# 433.net
KiCad netlist of a schematic drawn in EasyEDA Pro
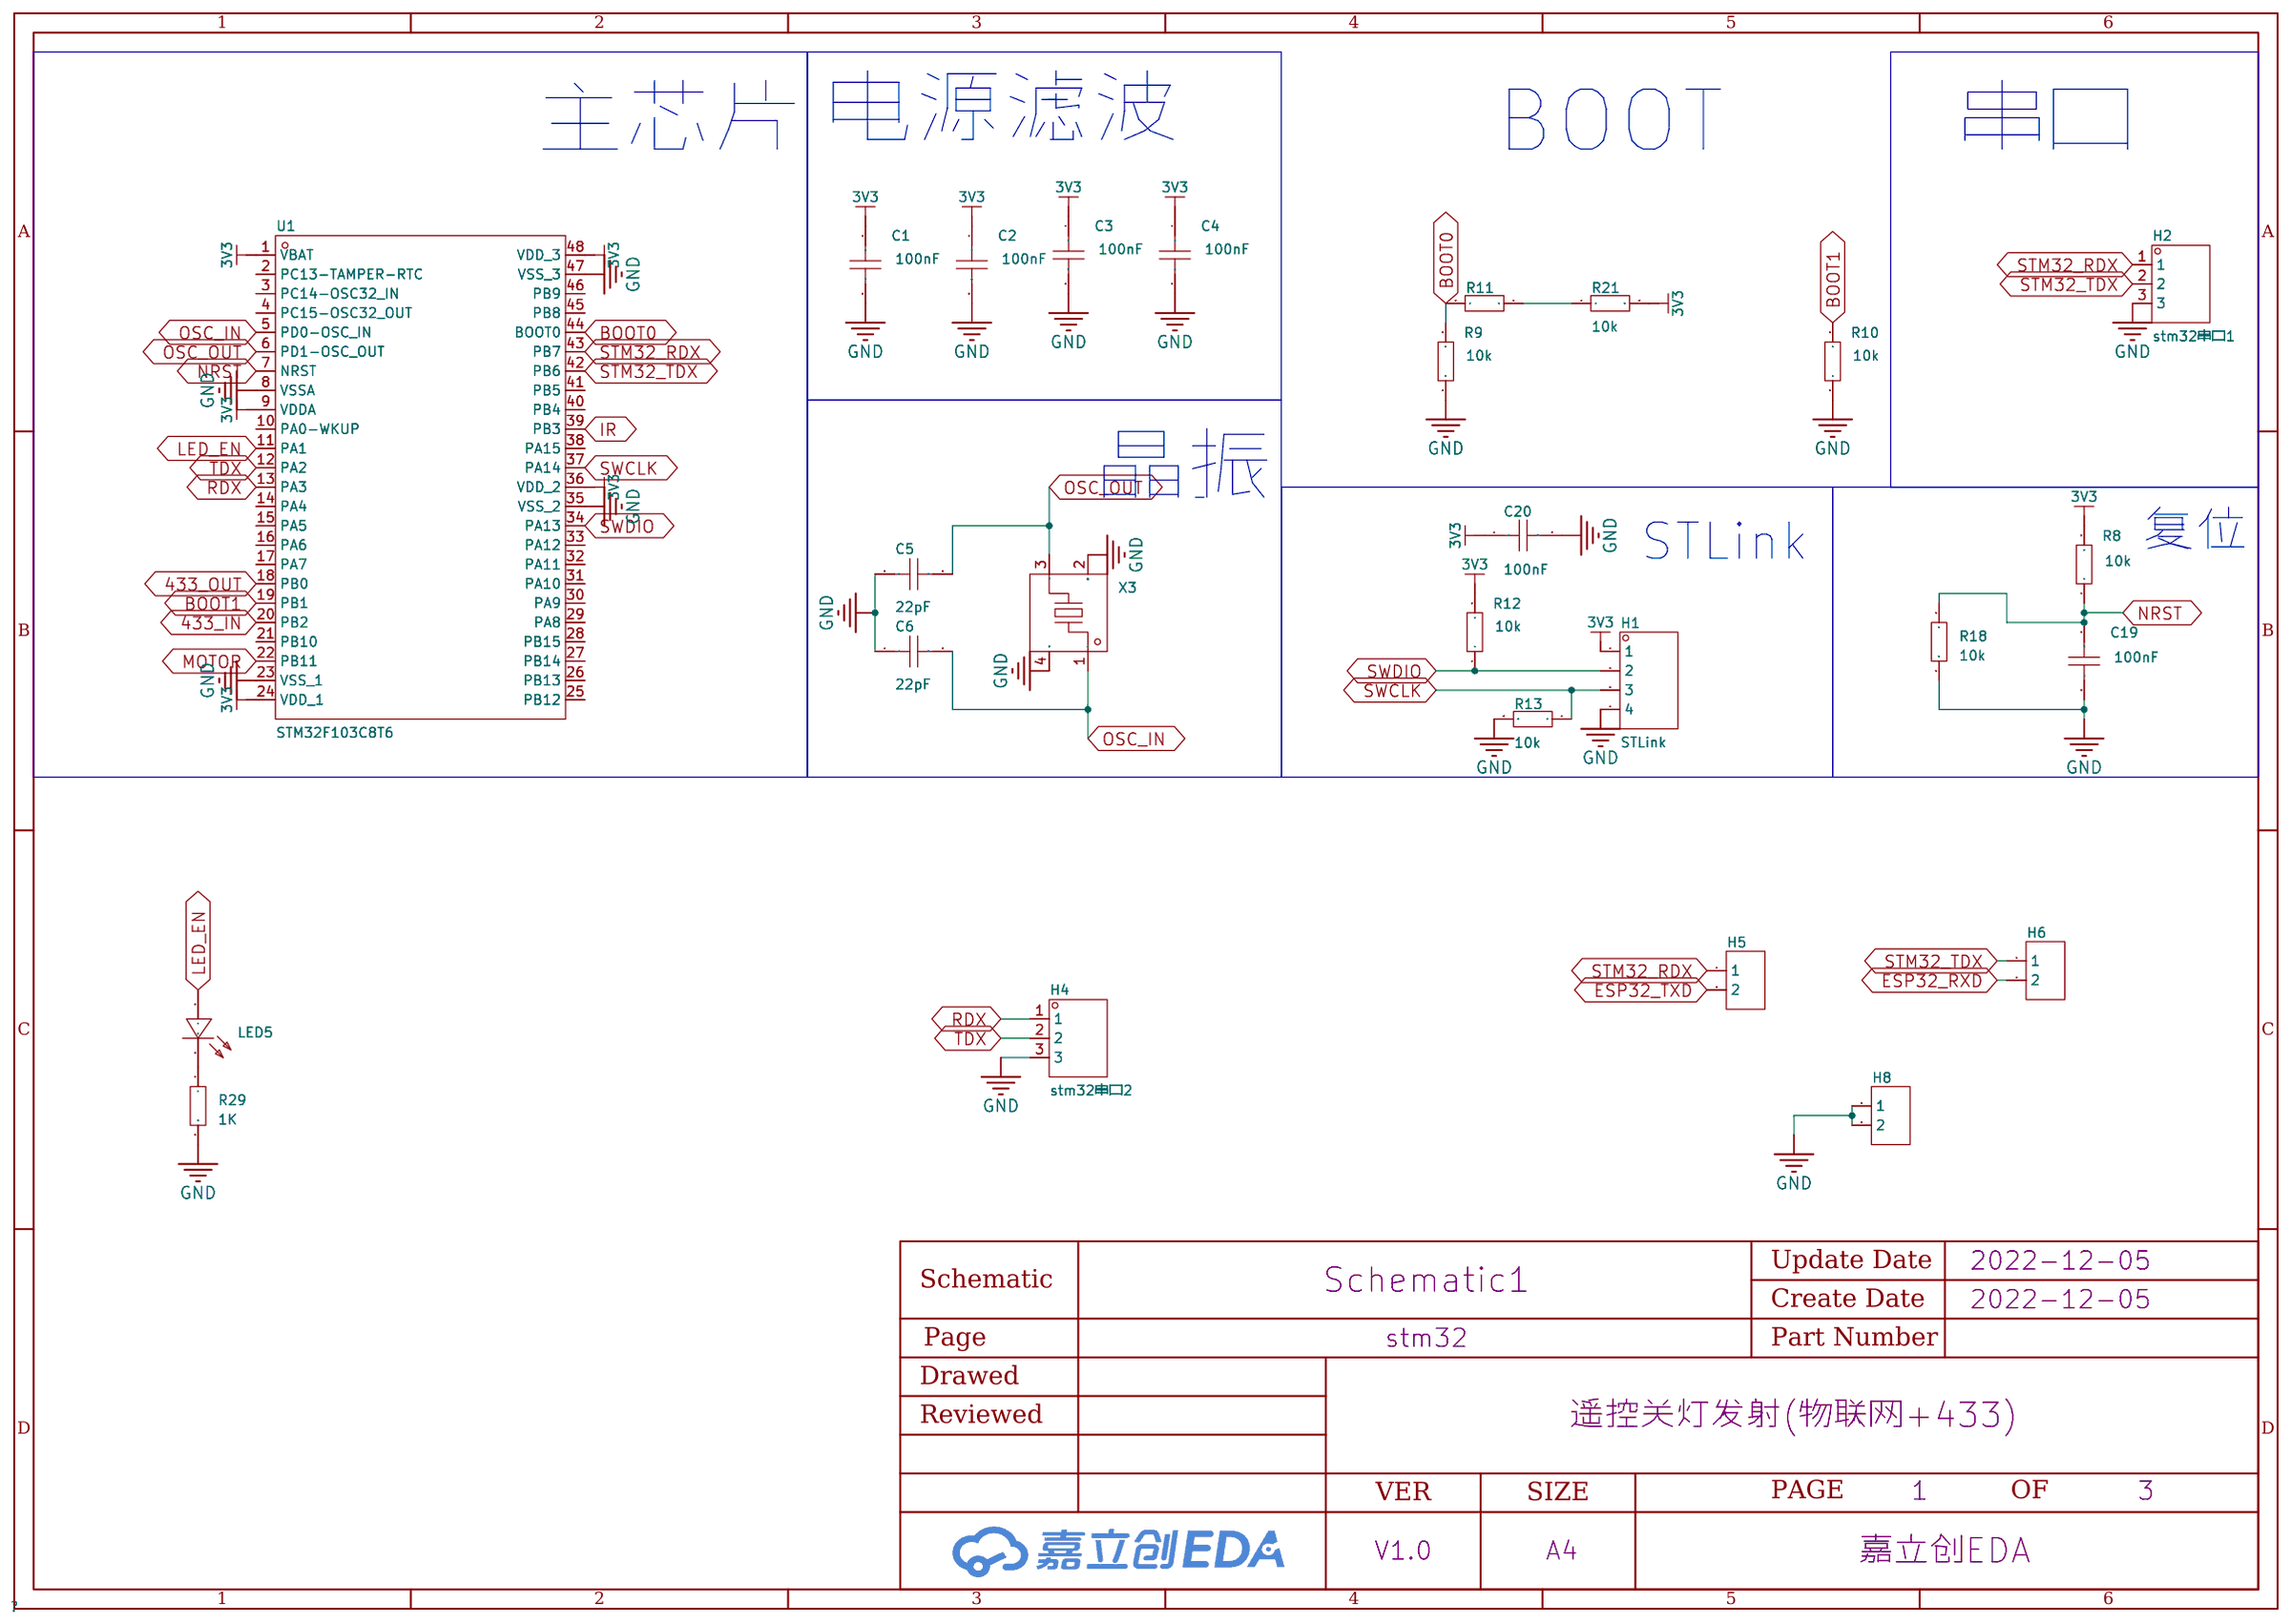
[diagram p0: stm32]
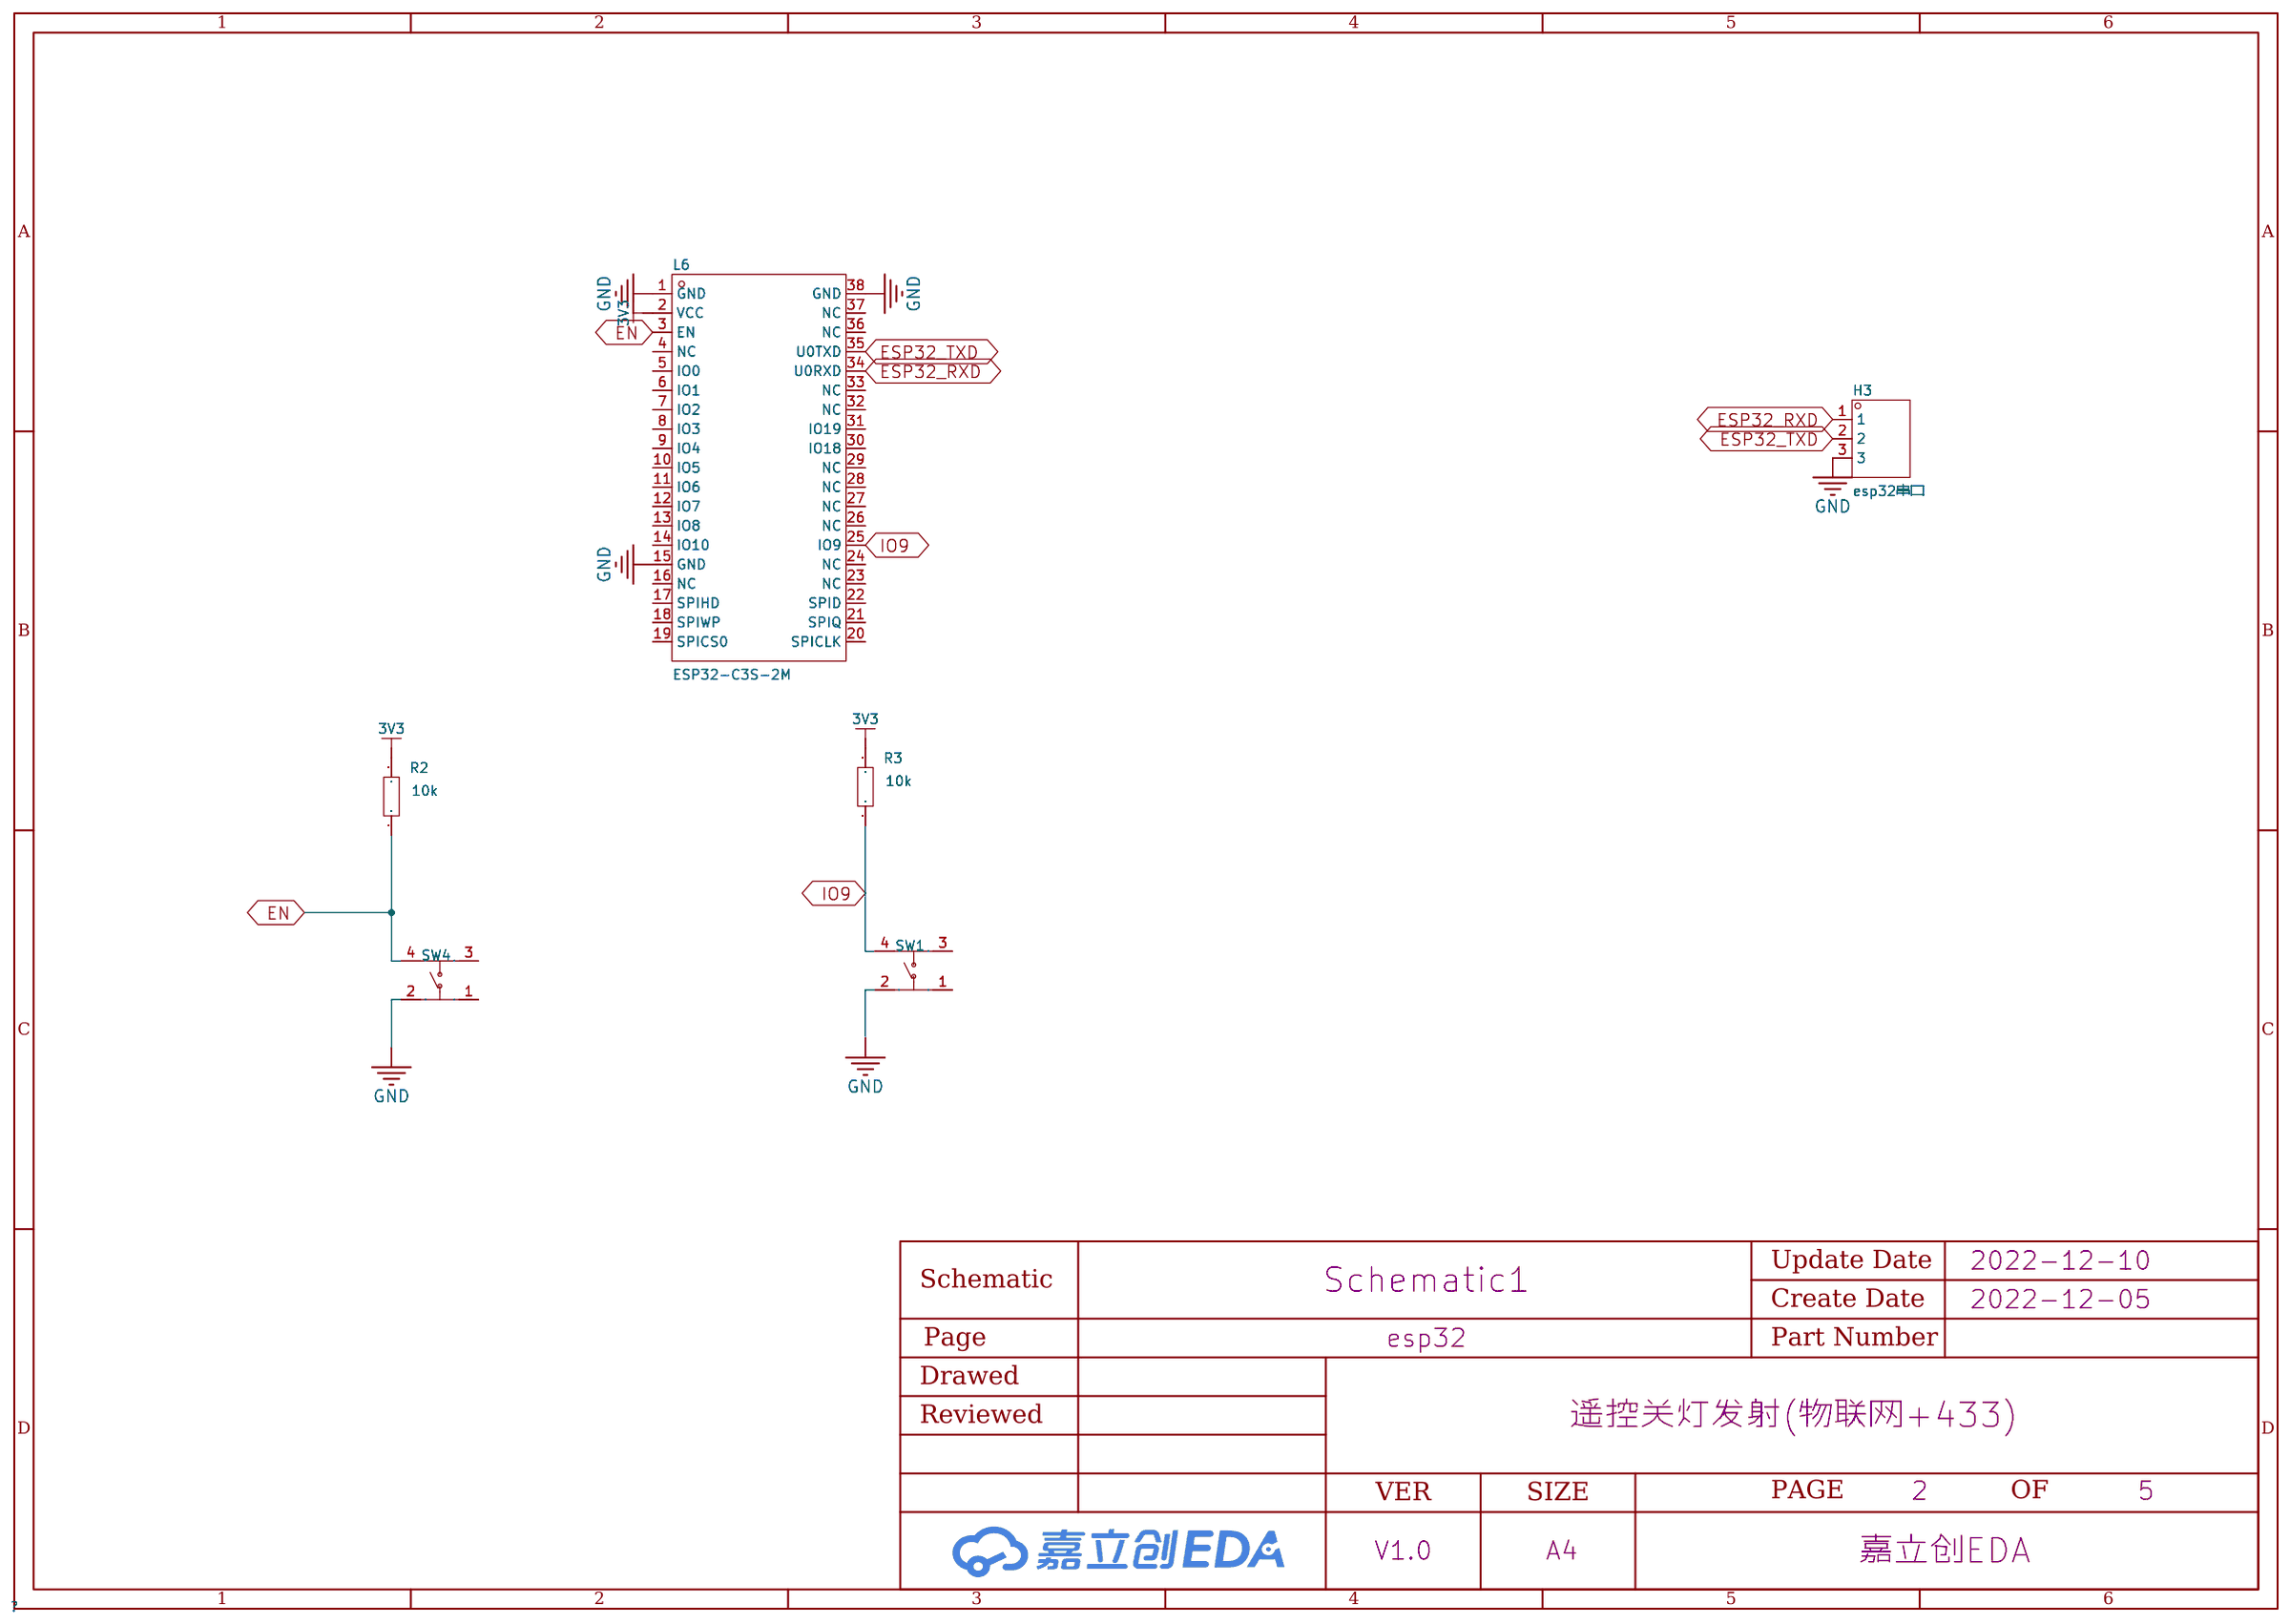
[diagram p1: esp32]
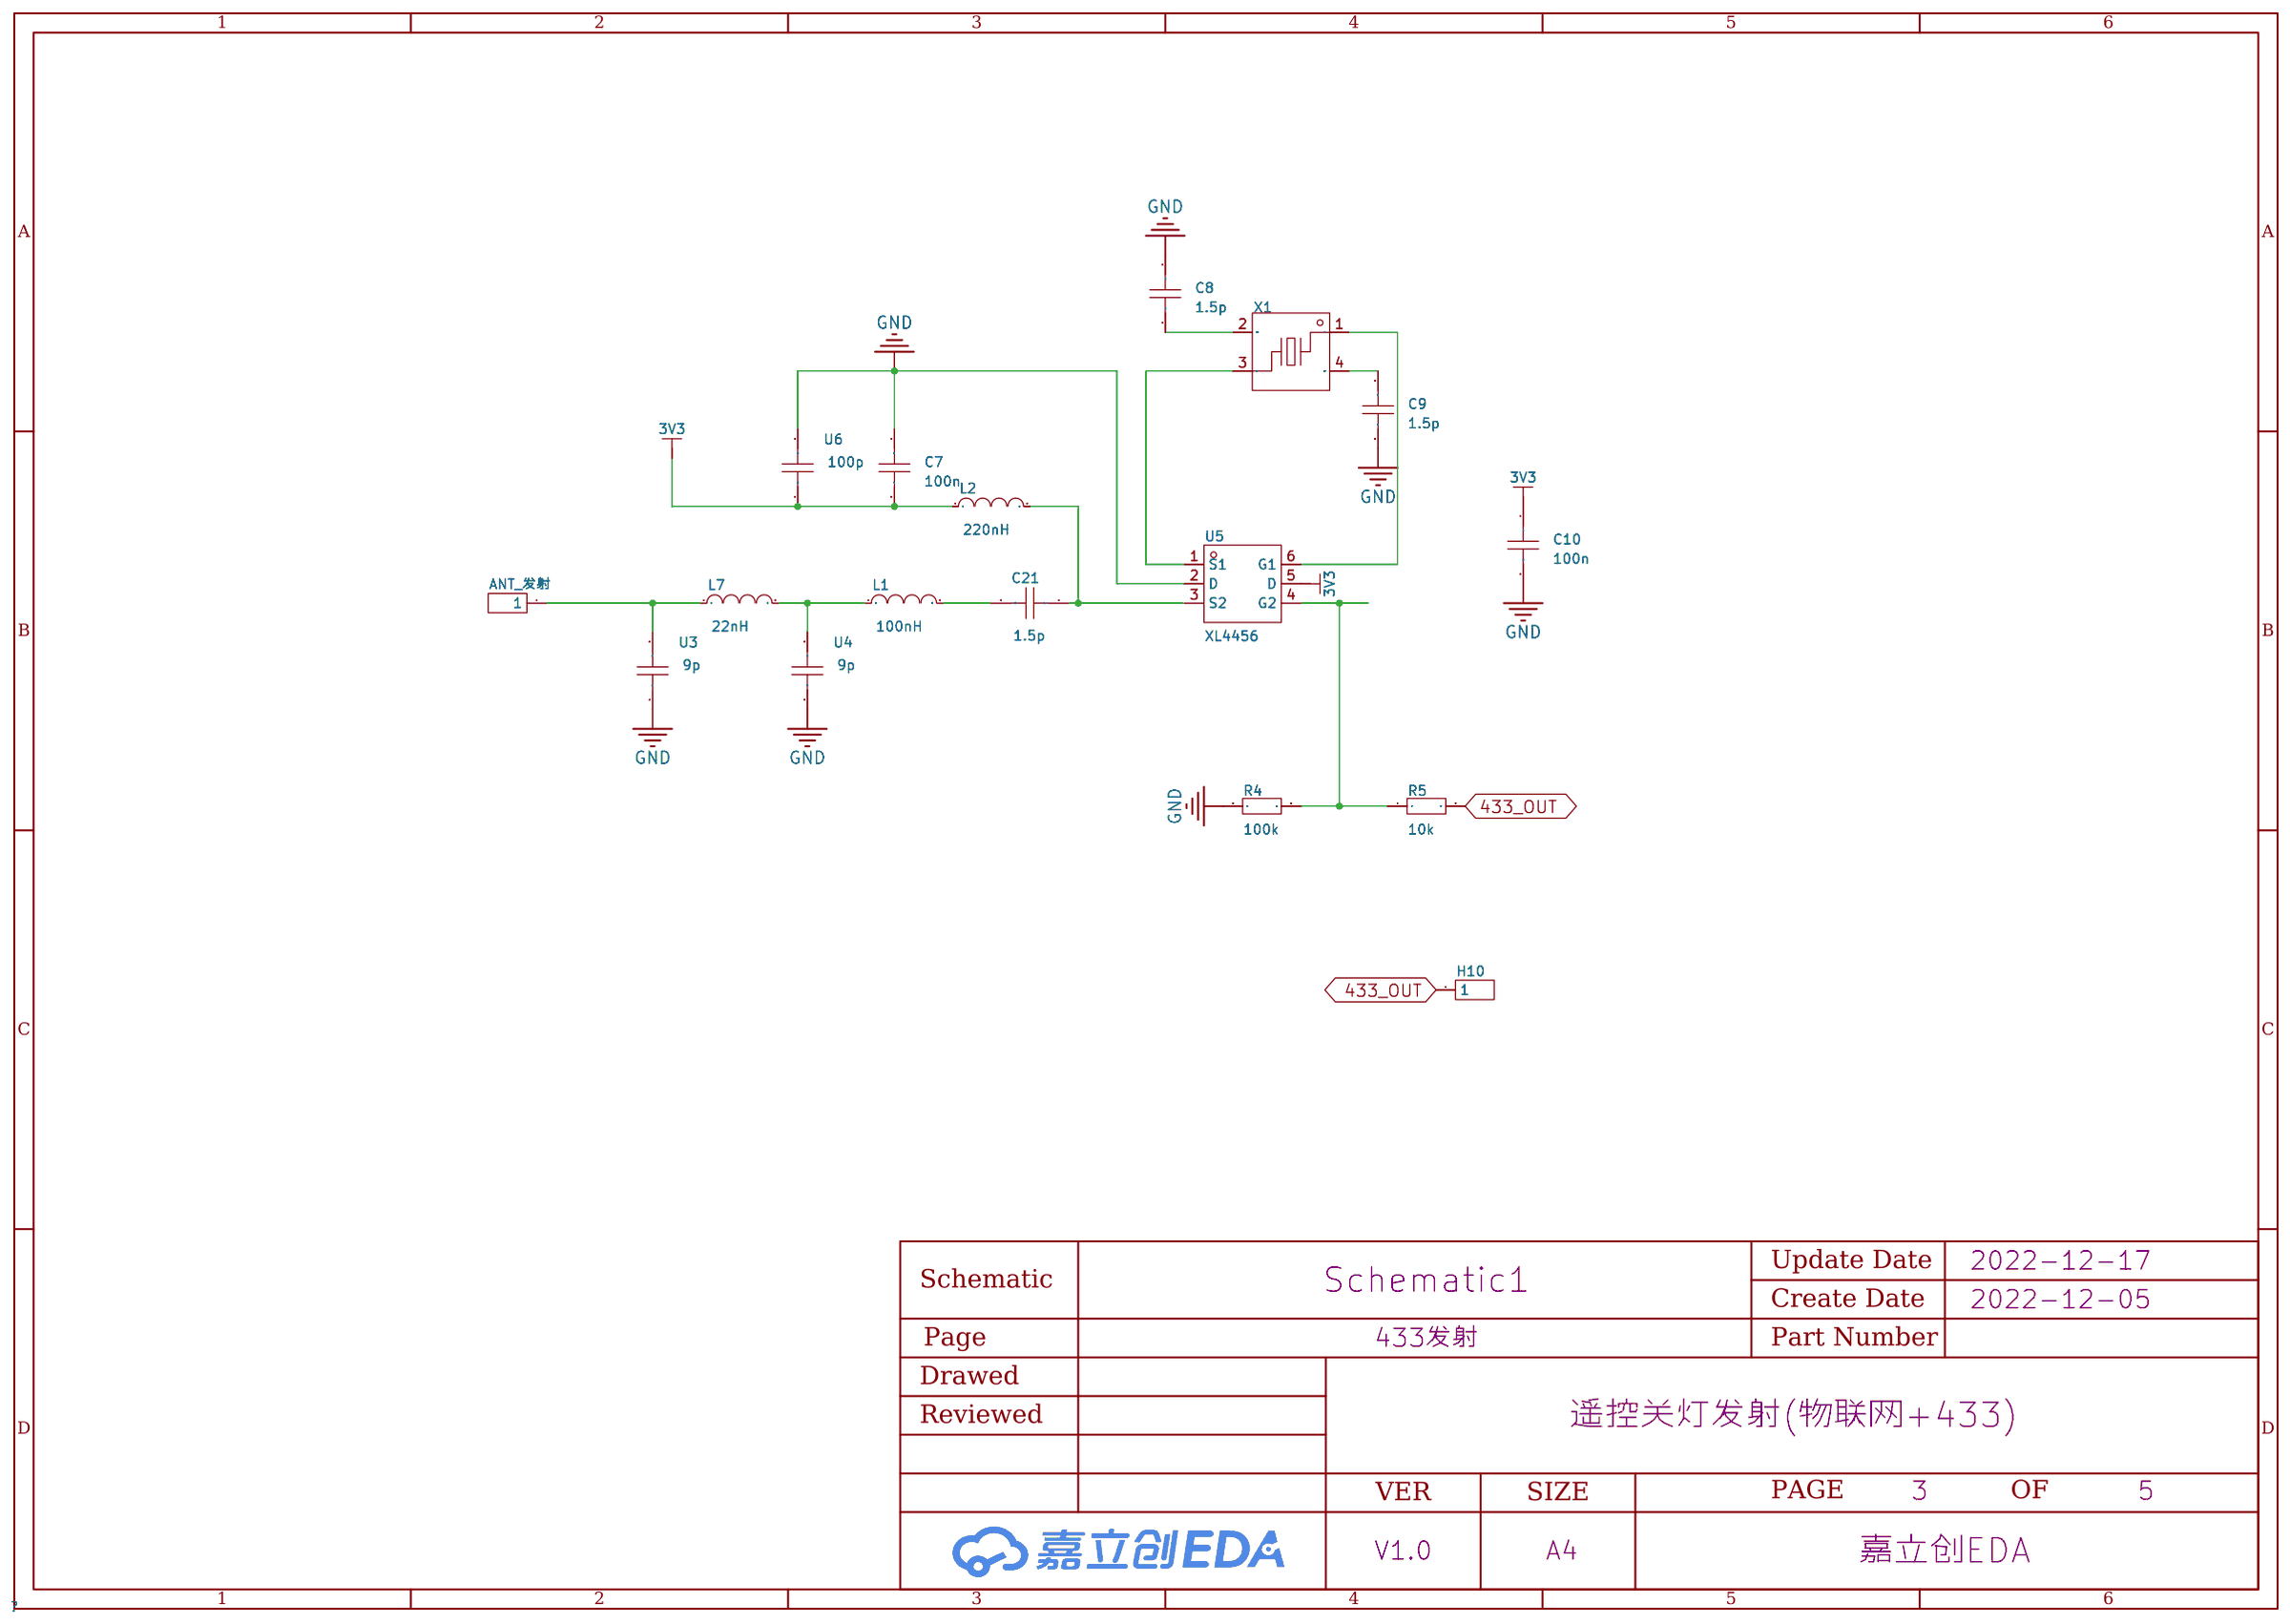
[diagram p2: 433发射]
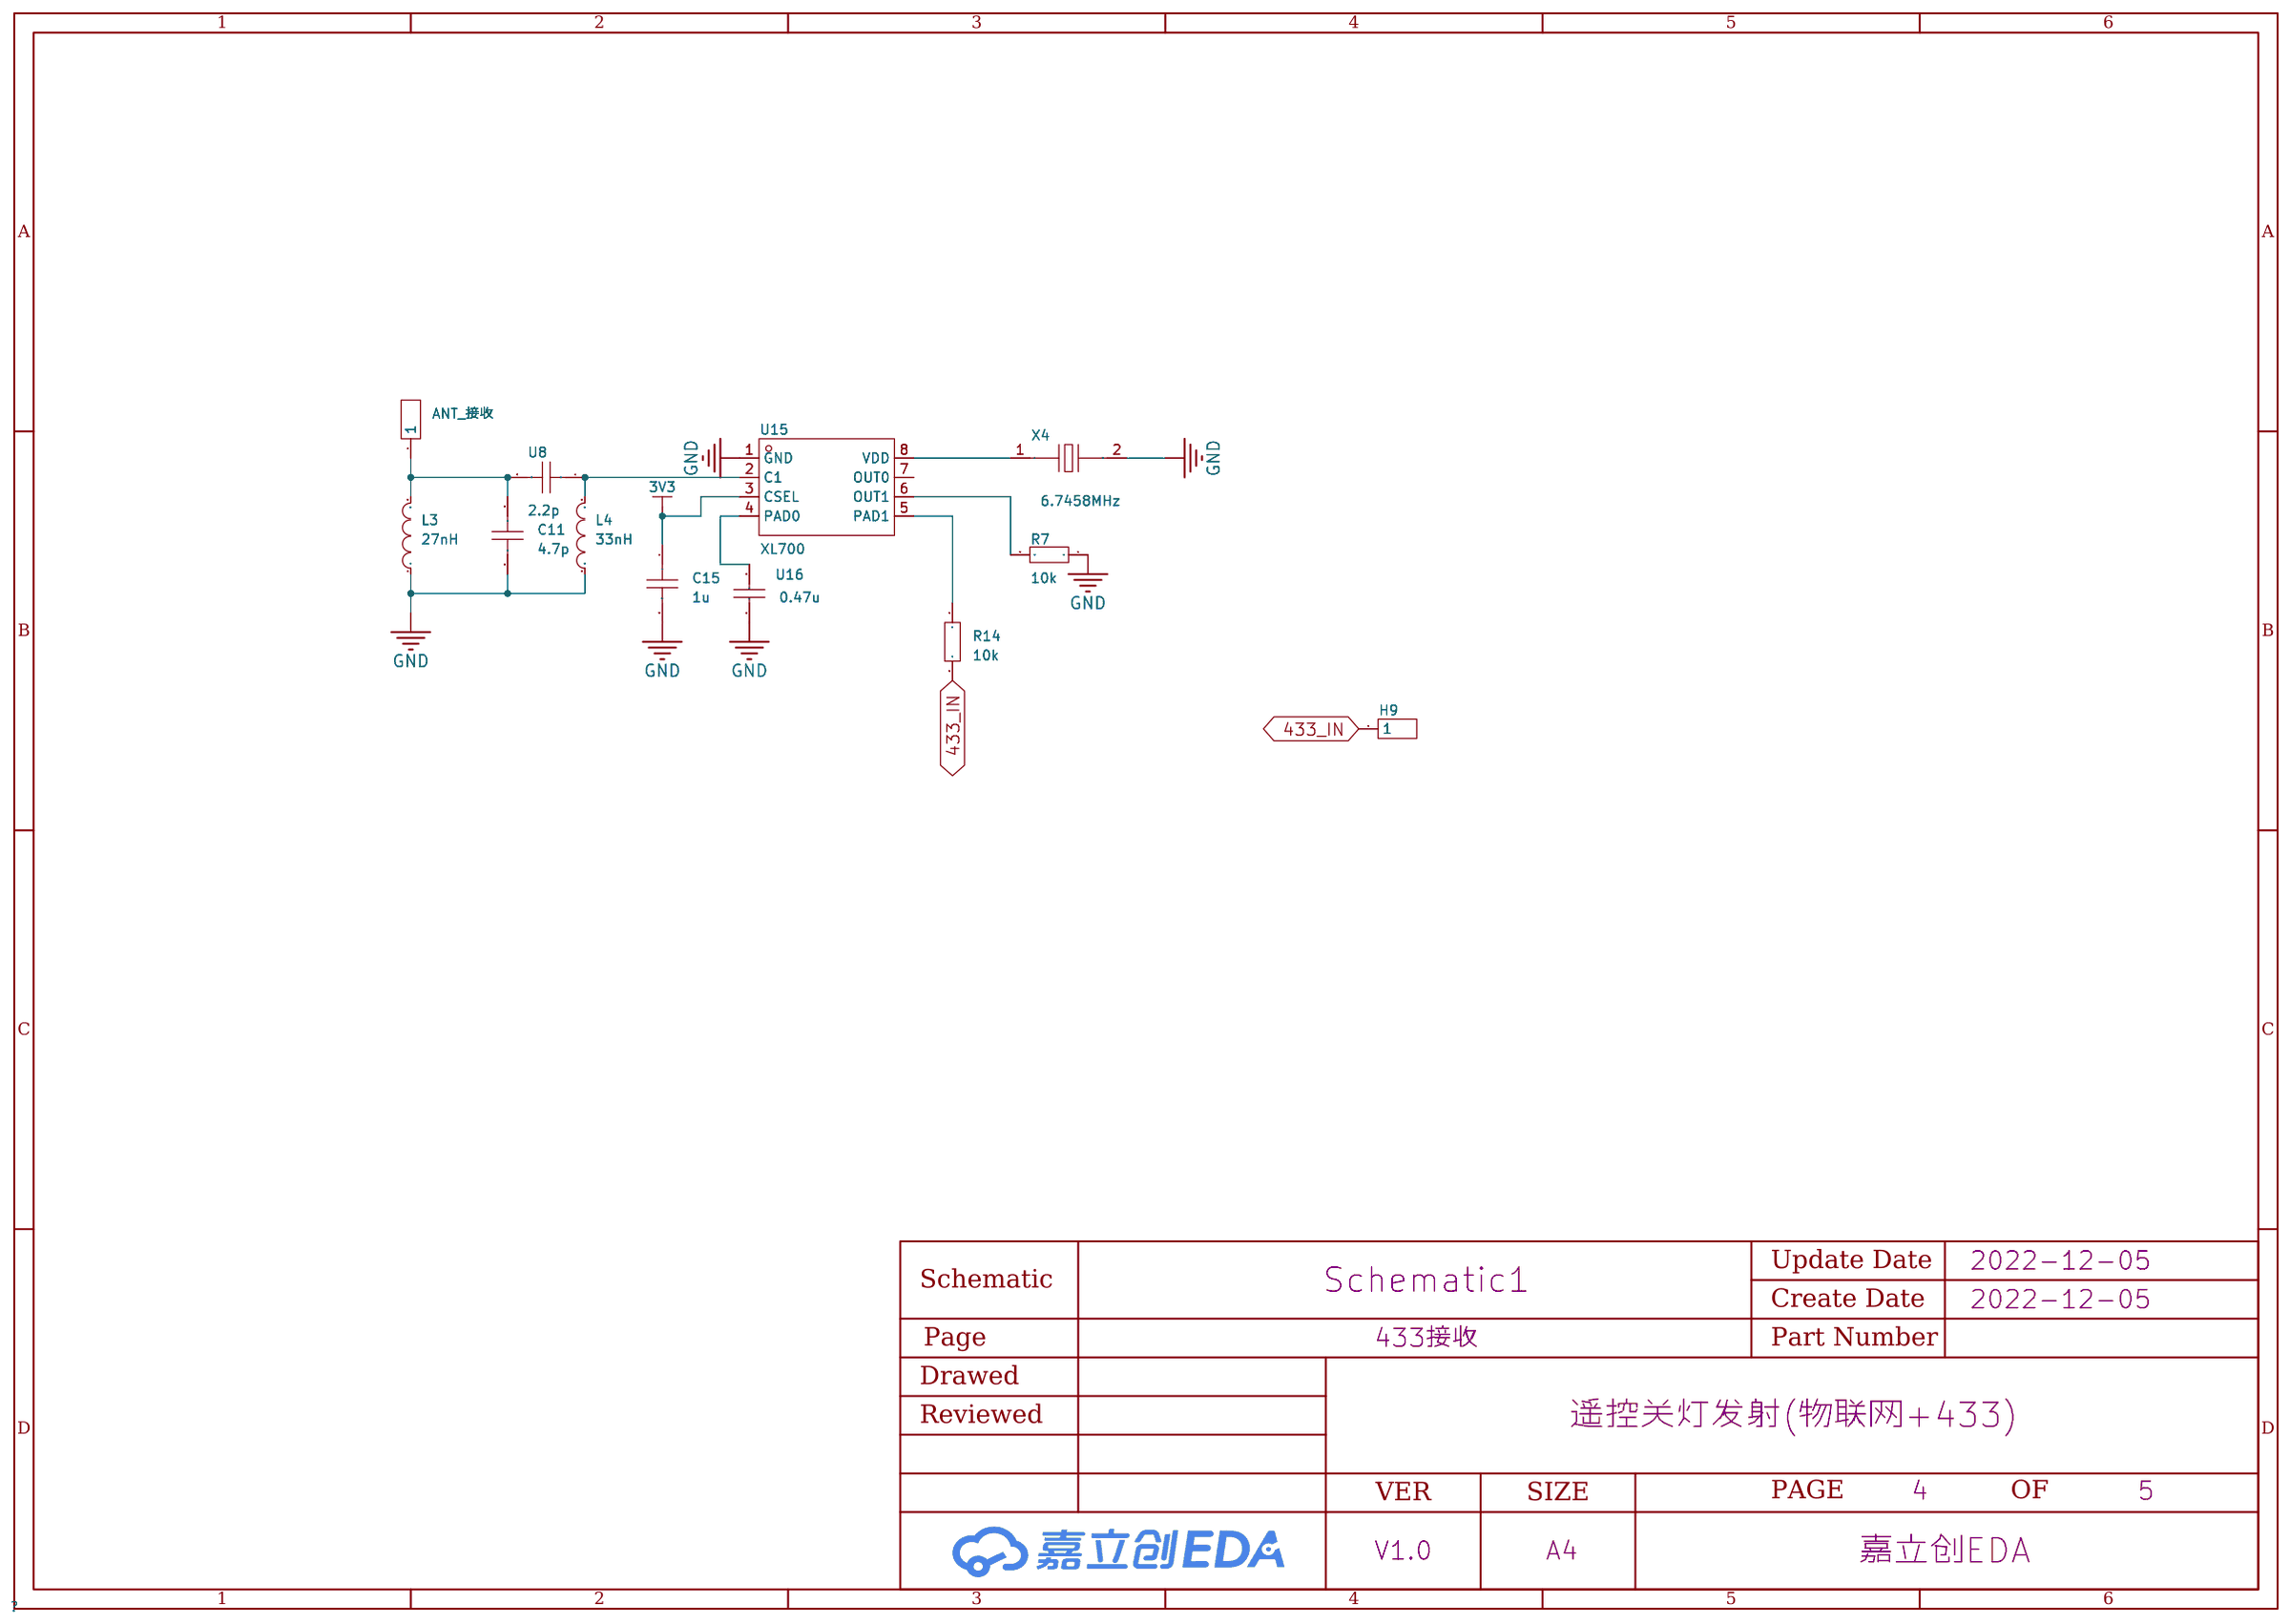
[diagram p3: 433接收]
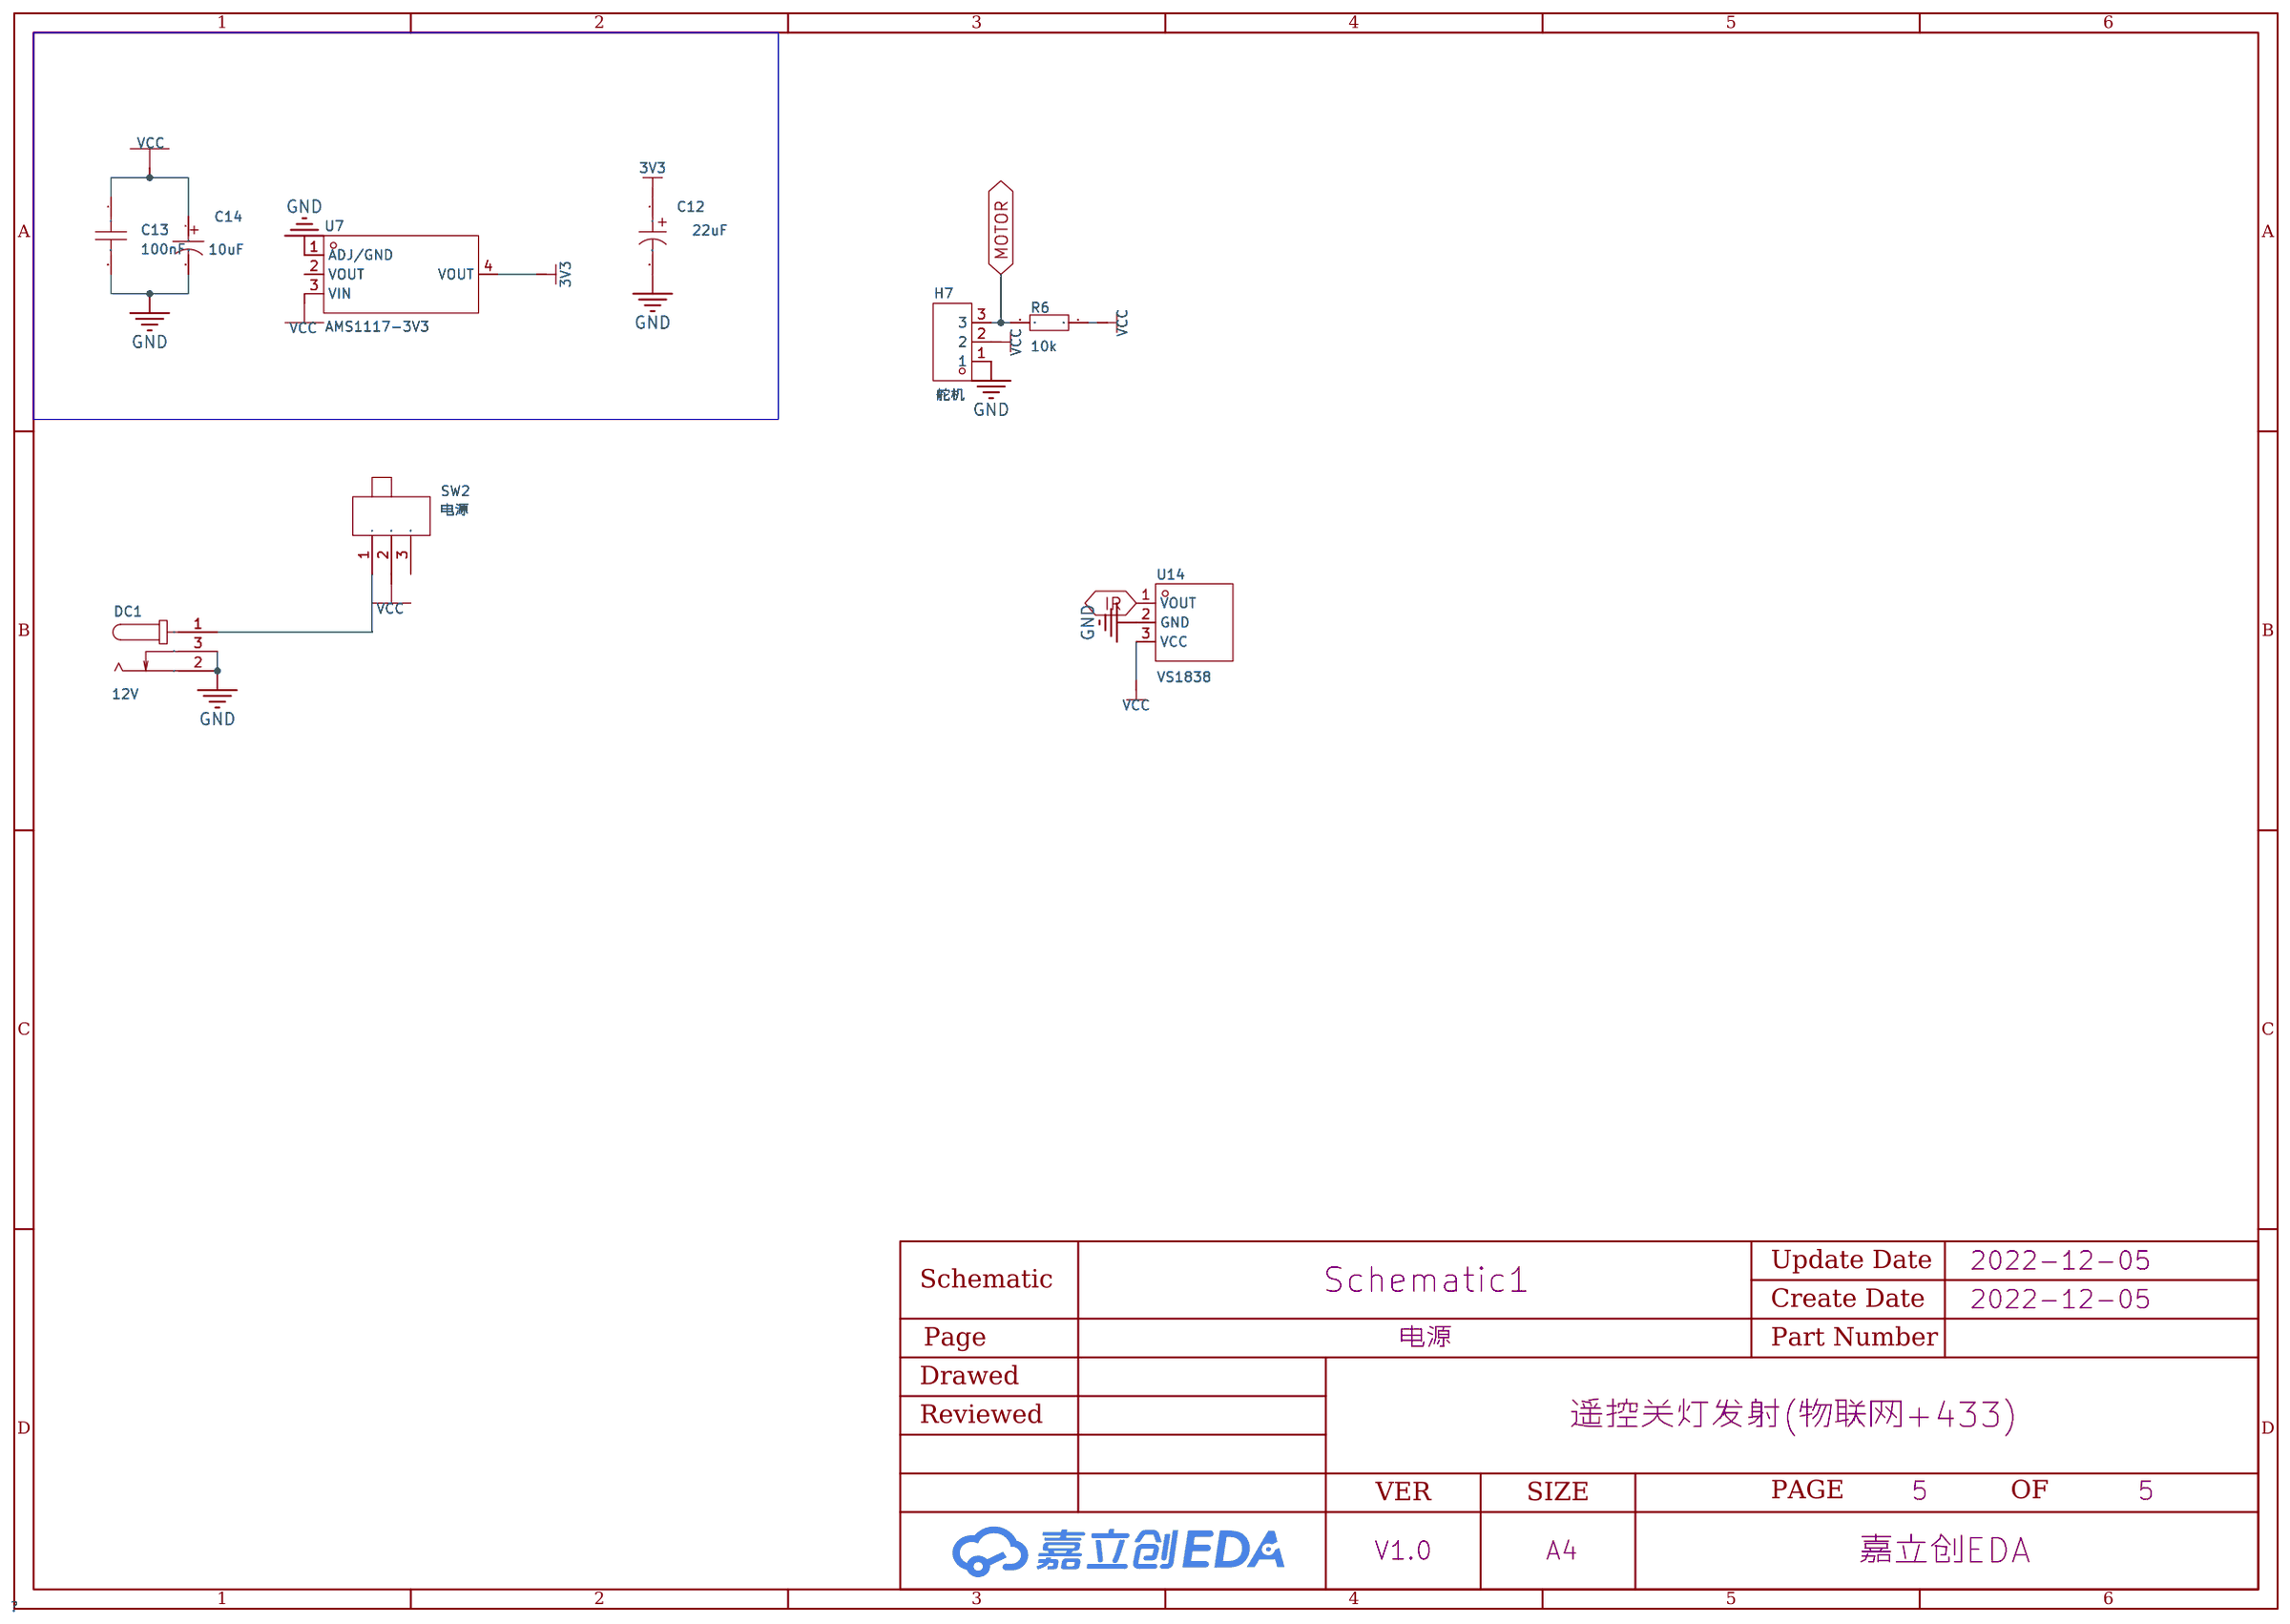
[diagram p4: 电源]

(export (version "E")
  (design (tool "Eeschema 10.0.6"))
  (components
    (comp (ref "C1")
      (value "100nF")
      (fields (field (name "Manufacturer Part") "0805"))
      (libsource (lib "easyedapro") (part "0805_C9900012713"))
    )
    (comp (ref "C2")
      (value "100nF")
      (fields (field (name "Manufacturer Part") "0805"))
      (libsource (lib "easyedapro") (part "0805_C9900012713"))
    )
    (comp (ref "C3")
      (value "100nF")
      (fields (field (name "Manufacturer Part") "0805"))
      (libsource (lib "easyedapro") (part "0805_C9900012713"))
    )
    (comp (ref "C4")
      (value "100nF")
      (fields (field (name "Manufacturer Part") "0805"))
      (libsource (lib "easyedapro") (part "0805_C9900012713"))
    )
    (comp (ref "C5")
      (value "22pF")
      (fields (field (name "Manufacturer Part") "0805"))
      (libsource (lib "easyedapro") (part "0805_C9900012713"))
    )
    (comp (ref "C6")
      (value "22pF")
      (fields (field (name "Manufacturer Part") "0805"))
      (libsource (lib "easyedapro") (part "0805_C9900012713"))
    )
    (comp (ref "C19")
      (value "100nF")
      (footprint "easyedapro:C0805")
      (fields (field (name "Manufacturer Part") "0805"))
      (libsource (lib "easyedapro") (part "0805_C9900012713"))
    )
    (comp (ref "C20")
      (value "100nF")
      (footprint "easyedapro:C0805")
      (fields (field (name "Manufacturer Part") "0805"))
      (libsource (lib "easyedapro") (part "0805_C9900012713"))
    )
    (comp (ref "H1")
      (value "STLink")
      (footprint "easyedapro:HDR-TH_4P-P2.54-V-M")
      (fields (field (name "Manufacturer Part") "B-2100S04P-A110") (field (name "Manufacturer") "Ckmtw(灿科盟)"))
      (libsource (lib "easyedapro") (part "Header-Male-2.54_1x4"))
    )
    (comp (ref "H2")
      (value "stm32串口1")
      (footprint "easyedapro:HDR-TH_3P-P2.54-V-M-1")
      (fields (field (name "Manufacturer Part") "77311-102-03LF") (field (name "Manufacturer") "Amphenol"))
      (libsource (lib "easyedapro") (part "77311-102-03LF"))
    )
    (comp (ref "H4")
      (value "stm32串口2")
      (footprint "easyedapro:HDR-TH_3P-P2.54-V-M-1")
      (fields (field (name "Manufacturer Part") "77311-102-03LF") (field (name "Manufacturer") "Amphenol"))
      (libsource (lib "easyedapro") (part "77311-102-03LF"))
    )
    (comp (ref "H5")
      (value "~")
      (footprint "easyedapro:HDR-TH_2P-P2.54-V-F")
      (libsource (lib "easyedapro") (part "Header-Female-2.54_1x2"))
    )
    (comp (ref "H6")
      (value "~")
      (footprint "easyedapro:HDR-TH_2P-P2.54-V-F")
      (libsource (lib "easyedapro") (part "Header-Female-2.54_1x2"))
    )
    (comp (ref "H8")
      (value "~")
      (footprint "easyedapro:HDR-TH_2P-P2.54-V-F")
      (libsource (lib "easyedapro") (part "Header-Female-2.54_1x2"))
    )
    (comp (ref "LED5")
      (value "~")
      (footprint "easyedapro:LED0805-R-RD")
      (description "发光颜色:翠绿;")
      (fields (field (name "Manufacturer Part") "NCD0805G1") (field (name "Manufacturer") "国星光电"))
      (libsource (lib "easyedapro") (part "FC-2012UGK-520D5"))
    )
    (comp (ref "R8")
      (value "10k")
      (footprint "easyedapro:R0805")
      (fields (field (name "Manufacturer Part") "0805"))
      (libsource (lib "easyedapro") (part "0805"))
    )
    (comp (ref "R9")
      (value "10k")
      (footprint "easyedapro:R0805")
      (fields (field (name "Manufacturer Part") "0805"))
      (libsource (lib "easyedapro") (part "0805"))
    )
    (comp (ref "R10")
      (value "10k")
      (footprint "easyedapro:R0805")
      (fields (field (name "Manufacturer Part") "0805"))
      (libsource (lib "easyedapro") (part "0805"))
    )
    (comp (ref "R11")
      (value "100R")
      (footprint "easyedapro:R0805")
      (fields (field (name "Manufacturer Part") "0805"))
      (libsource (lib "easyedapro") (part "0805"))
    )
    (comp (ref "R12")
      (value "10k")
      (footprint "easyedapro:R0805")
      (fields (field (name "Manufacturer Part") "0805"))
      (libsource (lib "easyedapro") (part "0805"))
    )
    (comp (ref "R13")
      (value "10k")
      (footprint "easyedapro:R0805")
      (fields (field (name "Manufacturer Part") "0805"))
      (libsource (lib "easyedapro") (part "0805"))
    )
    (comp (ref "R18")
      (value "10k")
      (footprint "easyedapro:R0805")
      (fields (field (name "Manufacturer Part") "0805"))
      (libsource (lib "easyedapro") (part "0805"))
    )
    (comp (ref "R21")
      (value "10k")
      (footprint "easyedapro:R0805")
      (fields (field (name "Manufacturer Part") "0805"))
      (libsource (lib "easyedapro") (part "0805"))
    )
    (comp (ref "R29")
      (value "1K")
      (footprint "easyedapro:R0805")
      (fields (field (name "Manufacturer Part") "0805"))
      (libsource (lib "easyedapro") (part "0805"))
    )
    (comp (ref "U1")
      (value "STM32F103C8T6")
      (footprint "easyedapro:LQFP-48_L7.0-W7.0-P0.50-LS9.0-BL")
      (description "CPU位数:32-Bit;ROM类型:FLASH;CPU内核:ARM® Cortex®-M3;主频（MAX):72MHz;工作电压:2V ~ 3.6V;")
      (fields (field (name "Manufacturer") "ST(意法半导体)"))
      (libsource (lib "easyedapro") (part "STM32F103C8T6"))
    )
    (comp (ref "X3")
      (value "NX3225SA-26MHz-STD-CSR-6")
      (footprint "easyedapro:CRYSTAL-SMD_4P-L3.2-W2.5-BL")
      (fields (field (name "Manufacturer") "NDK"))
      (libsource (lib "easyedapro") (part "NX3225SA-26MHZ-STD-CSR-6"))
    )
    (comp (ref "H3")
      (value "esp32串口")
      (footprint "easyedapro:HDR-TH_3P-P2.54-V-M-1")
      (fields (field (name "Manufacturer Part") "77311-102-03LF") (field (name "Manufacturer") "Amphenol"))
      (libsource (lib "easyedapro") (part "77311-102-03LF"))
    )
    (comp (ref "L6")
      (value "ESP32-C3S-2M")
      (footprint "easyedapro:WIFIM-SMD_ESP32-C3S-2M")
      (fields (field (name "Manufacturer") "Ai-Thinker(安信可)"))
      (libsource (lib "easyedapro") (part "ESP32-C3S-2M"))
    )
    (comp (ref "R2")
      (value "10k")
      (footprint "easyedapro:R0805")
      (fields (field (name "Manufacturer Part") "0805"))
      (libsource (lib "easyedapro") (part "0805"))
    )
    (comp (ref "R3")
      (value "10k")
      (footprint "easyedapro:R0805")
      (fields (field (name "Manufacturer Part") "0805"))
      (libsource (lib "easyedapro") (part "0805"))
    )
    (comp (ref "SW1")
      (value "MPU6050")
      (footprint "easyedapro:SW-SMD_4P-L6.0-W6.0-P4.50-LS9.0-2")
      (fields
        (field (name "Manufacturer Part") "KH-6X6X5H-STM")
        (field (name "Manufacturer") "kinghelm(金航标)")
      )
      (libsource (lib "easyedapro") (part "KH-6X6X5H-STM"))
    )
    (comp (ref "SW4")
      (value "MPU6050")
      (footprint "easyedapro:SW-SMD_4P-L6.0-W6.0-P4.50-LS9.0-2")
      (fields
        (field (name "Manufacturer Part") "KH-6X6X5H-STM")
        (field (name "Manufacturer") "kinghelm(金航标)")
      )
      (libsource (lib "easyedapro") (part "KH-6X6X5H-STM"))
    )
    (comp (ref "ANT_发射")
      (value "~")
      (footprint "easyedapro:HDR-TH_1P-V-M_XKB_X4611WV-01I-C28D40")
      (libsource (lib "easyedapro") (part "HDR_1x1"))
    )
    (comp (ref "C7")
      (value "100n")
      (footprint "easyedapro:C0805")
      (fields (field (name "Manufacturer Part") "0805"))
      (libsource (lib "easyedapro") (part "0805_C9900012713"))
    )
    (comp (ref "C8")
      (value "1.5p")
      (footprint "easyedapro:C0805")
      (fields (field (name "Manufacturer Part") "0805"))
      (libsource (lib "easyedapro") (part "0805_C9900012713"))
    )
    (comp (ref "C9")
      (value "1.5p")
      (footprint "easyedapro:C0805")
      (fields (field (name "Manufacturer Part") "0805"))
      (libsource (lib "easyedapro") (part "0805_C9900012713"))
    )
    (comp (ref "C10")
      (value "100n")
      (footprint "easyedapro:C0805")
      (fields (field (name "Manufacturer Part") "0805"))
      (libsource (lib "easyedapro") (part "0805_C9900012713"))
    )
    (comp (ref "C21")
      (value "1.5p")
      (footprint "easyedapro:C0805")
      (fields (field (name "Manufacturer Part") "0805"))
      (libsource (lib "easyedapro") (part "0805_C9900012713"))
    )
    (comp (ref "H10")
      (value "~")
      (footprint "easyedapro:HDR-TH_1P-V-M_XKB_X4611WV-01I-C28D40")
      (libsource (lib "easyedapro") (part "HDR_1x1"))
    )
    (comp (ref "L1")
      (value "100nH")
      (footprint "easyedapro:IND-SMD_L1.7-W1.0-SCW1608C39NJST")
      (fields (field (name "Manufacturer Part") "L0603"))
      (libsource (lib "easyedapro") (part "L0603_C9900016892"))
    )
    (comp (ref "L2")
      (value "220nH")
      (footprint "easyedapro:IND-SMD_L1.7-W1.0-SCW1608C39NJST")
      (fields (field (name "Manufacturer Part") "L0603"))
      (libsource (lib "easyedapro") (part "L0603_C9900016892"))
    )
    (comp (ref "L7")
      (value "22nH")
      (footprint "easyedapro:IND-SMD_L1.7-W1.0-SCW1608C39NJST")
      (fields (field (name "Manufacturer Part") "L0603"))
      (libsource (lib "easyedapro") (part "L0603_C9900016892"))
    )
    (comp (ref "R4")
      (value "100k")
      (footprint "easyedapro:R0805")
      (fields (field (name "Manufacturer Part") "0805"))
      (libsource (lib "easyedapro") (part "0805"))
    )
    (comp (ref "R5")
      (value "10k")
      (footprint "easyedapro:R0805")
      (fields (field (name "Manufacturer Part") "0805"))
      (libsource (lib "easyedapro") (part "0805"))
    )
    (comp (ref "U3")
      (value "9p")
      (footprint "easyedapro:C0603")
      (fields (field (name "Manufacturer Part") "104P"))
      (libsource (lib "easyedapro") (part "104P"))
    )
    (comp (ref "U4")
      (value "9p")
      (footprint "easyedapro:C0603")
      (fields (field (name "Manufacturer Part") "104P"))
      (libsource (lib "easyedapro") (part "104P"))
    )
    (comp (ref "U5")
      (value "XL4456")
      (footprint "easyedapro:SOT-23-6_L2.9-W1.6-P0.95-LS2.9-BL")
      (fields (field (name "Manufacturer Part") "JMTM8205A") (field (name "Manufacturer") "JJW(捷捷微)"))
      (libsource (lib "easyedapro") (part "JMTM8205A"))
    )
    (comp (ref "U6")
      (value "100p")
      (footprint "easyedapro:C0603")
      (fields (field (name "Manufacturer Part") "104P"))
      (libsource (lib "easyedapro") (part "104P"))
    )
    (comp (ref "X1")
      (value "NX3225SA-26MHz-STD-CSR-6")
      (footprint "easyedapro:CRYSTAL-SMD_4P-L3.2-W2.5-BL")
      (fields (field (name "Manufacturer") "NDK"))
      (libsource (lib "easyedapro") (part "NX3225SA-26MHZ-STD-CSR-6"))
    )
    (comp (ref "ANT_接收")
      (value "~")
      (footprint "easyedapro:HDR-TH_1P-V-M_XKB_X4611WV-01I-C28D40")
      (libsource (lib "easyedapro") (part "HDR_1x1"))
    )
    (comp (ref "C11")
      (value "4.7p")
      (footprint "easyedapro:C0805")
      (fields (field (name "Manufacturer Part") "0805"))
      (libsource (lib "easyedapro") (part "0805_C9900012713"))
    )
    (comp (ref "C15")
      (value "1u")
      (footprint "easyedapro:C0805")
      (fields (field (name "Manufacturer Part") "0805"))
      (libsource (lib "easyedapro") (part "0805_C9900012713"))
    )
    (comp (ref "H9")
      (value "~")
      (footprint "easyedapro:HDR-TH_1P-V-M_XKB_X4611WV-01I-C28D40")
      (libsource (lib "easyedapro") (part "HDR_1x1"))
    )
    (comp (ref "L3")
      (value "27nH")
      (footprint "easyedapro:IND-SMD_L1.7-W1.0-SCW1608C39NJST")
      (fields (field (name "Manufacturer Part") "L0603"))
      (libsource (lib "easyedapro") (part "L0603_C9900016892"))
    )
    (comp (ref "L4")
      (value "33nH")
      (footprint "easyedapro:IND-SMD_L1.7-W1.0-SCW1608C39NJST")
      (fields (field (name "Manufacturer Part") "L0603"))
      (libsource (lib "easyedapro") (part "L0603_C9900016892"))
    )
    (comp (ref "R7")
      (value "10k")
      (footprint "easyedapro:R0805")
      (fields (field (name "Manufacturer Part") "0805"))
      (libsource (lib "easyedapro") (part "0805"))
    )
    (comp (ref "R14")
      (value "10k")
      (footprint "easyedapro:R0805")
      (fields (field (name "Manufacturer Part") "0805"))
      (libsource (lib "easyedapro") (part "0805"))
    )
    (comp (ref "U8")
      (value "2.2p")
      (footprint "easyedapro:C0603")
      (fields (field (name "Manufacturer Part") "104P"))
      (libsource (lib "easyedapro") (part "104P"))
    )
    (comp (ref "U15")
      (value "XL700")
      (footprint "easyedapro:SOP-8_L4.9-W3.9-P1.27-LS6.0-BL")
      (fields (field (name "Manufacturer Part") "XW02E SOP8") (field (name "Manufacturer") "Sam&wing(芯网)"))
      (libsource (lib "easyedapro") (part "XW02E SOP8"))
    )
    (comp (ref "U16")
      (value "0.47u")
      (footprint "easyedapro:C0402")
      (fields (field (name "Manufacturer Part") "16p"))
      (libsource (lib "easyedapro") (part "16P"))
    )
    (comp (ref "X4")
      (value "6.7458MHz")
      (footprint "easyedapro:OSC-SMD_2P-L11.4-W4.7-LS12.3")
      (description "晶振类型:-;频率:-;负载电容:-;工作温度:-;")
      (fields
        (field (name "Manufacturer Part") "49SMD-4MHZ-15PF-20PPM")
        (field (name "Manufacturer") "TKD(泰晶)")
      )
      (libsource (lib "easyedapro") (part "49SMD-4MHZ-15PF-20PPM"))
    )
    (comp (ref "C12")
      (value "22uF")
      (footprint "easyedapro:CAP-TH_BD5.0-P2.00-D0.6-FD")
      (fields
        (field (name "Manufacturer Part") "LW220M0500511PV2-D5")
        (field (name "Manufacturer") "UNITED(怡德)")
      )
      (libsource (lib "easyedapro") (part "LW220M0500511PV2-D5"))
    )
    (comp (ref "C13")
      (value "100nF")
      (footprint "easyedapro:C0805")
      (fields (field (name "Manufacturer Part") "0805"))
      (libsource (lib "easyedapro") (part "0805_C9900012713"))
    )
    (comp (ref "C14")
      (value "10uF")
      (footprint "easyedapro:CAP-TH_BD5.0-P2.00-D0.8-FD")
      (fields
        (field (name "Manufacturer Part") "KM106M025D11RR0VH2FP0")
        (field (name "Manufacturer") "CX(承兴)")
      )
      (libsource (lib "easyedapro") (part "10uF 25V 5*11"))
    )
    (comp (ref "DC1")
      (value "12V")
      (footprint "easyedapro:DC-IN-TH_DC005-T20")
      (description "连接器类型:DC电源插座;安装方式:弯插;触点内径:-;触点外径:6.3mm;额定电流:3A;额定电压:30V;工作温度范围:-10~+60;")
      (fields (field (name "Manufacturer Part") "DC005-T20") (field (name "Manufacturer") "SOFNG(硕方)"))
      (libsource (lib "easyedapro") (part "DC005-2.0MM"))
    )
    (comp (ref "H7")
      (value "舵机")
      (footprint "easyedapro:HDR-TH_3P-P2.54-V-F")
      (libsource (lib "easyedapro") (part "PM254V-11-03-H85"))
    )
    (comp (ref "R6")
      (value "10k")
      (footprint "easyedapro:R0805")
      (fields (field (name "Manufacturer Part") "0805"))
      (libsource (lib "easyedapro") (part "0805"))
    )
    (comp (ref "SW2")
      (value "电源")
      (footprint "easyedapro:SW-TH_MK-12D18-G040")
      (fields (field (name "Manufacturer Part") "MK-12D18-G020") (field (name "Manufacturer") "G-Switch(品赞)"))
      (libsource (lib "easyedapro") (part "MK-12D18-G020"))
    )
    (comp (ref "U7")
      (value "AMS1117-3V3")
      (footprint "easyedapro:SOT-223-3_L6.7-W3.7-P2.30-LS7.0-BR")
      (description "静态电流(Iq):-;输出类型:固定;最大输入电压:18V;输出电压(可调):-;压降(max):1.5V @ 1A;输出电压(固定):5V;")
      (fields (field (name "Manufacturer Part") "AMS1117-5.0") (field (name "Manufacturer") "Slkor(萨科微)"))
      (libsource (lib "easyedapro") (part "AMS1117-5.0_C473812"))
    )
    (comp (ref "U14")
      (value "VS1838")
      (footprint "easyedapro:OPTO-TH_3P-L7.0-W5.6-P2.54-L")
      (fields (field (name "Manufacturer Part") "DY-IRM-AC01-AN") (field (name "Manufacturer") "TONYU(东裕)"))
      (libsource (lib "easyedapro") (part "DY-IRM-AC01-AN"))
    )
  )
  (nets
    (net (code "1") (name "3V3") (class "Default")
      (node (ref "C1") (pin "1") (pinfunction "1_1") (pintype "input"))
      (node (ref "C10") (pin "1") (pinfunction "1_1") (pintype "input"))
      (node (ref "C12") (pin "1") (pinfunction "1_1") (pintype "input"))
      (node (ref "C15") (pin "1") (pinfunction "1_1") (pintype "input"))
      (node (ref "C2") (pin "1") (pinfunction "1_1") (pintype "input"))
      (node (ref "C20") (pin "1") (pinfunction "1_1") (pintype "input"))
      (node (ref "C3") (pin "1") (pinfunction "1_1") (pintype "input"))
      (node (ref "C4") (pin "1") (pinfunction "1_1") (pintype "input"))
      (node (ref "C7") (pin "2") (pinfunction "2_2") (pintype "input"))
      (node (ref "H1") (pin "1") (pinfunction "1_1") (pintype "input"))
      (node (ref "L2") (pin "1") (pinfunction "1_1") (pintype "input"))
      (node (ref "L6") (pin "2") (pinfunction "VCC_2") (pintype "input"))
      (node (ref "R12") (pin "2") (pinfunction "2_2") (pintype "input"))
      (node (ref "R2") (pin "2") (pinfunction "2_2") (pintype "input"))
      (node (ref "R21") (pin "2") (pinfunction "2_2") (pintype "input"))
      (node (ref "R3") (pin "2") (pinfunction "2_2") (pintype "input"))
      (node (ref "R8") (pin "2") (pinfunction "2_2") (pintype "input"))
      (node (ref "U1") (pin "1") (pinfunction "VBAT_1") (pintype "input"))
      (node (ref "U1") (pin "24") (pinfunction "VDD_1_24") (pintype "input"))
      (node (ref "U1") (pin "36") (pinfunction "VDD_2_36") (pintype "input"))
      (node (ref "U1") (pin "48") (pinfunction "VDD_3_48") (pintype "input"))
      (node (ref "U1") (pin "9") (pinfunction "VDDA_9") (pintype "input"))
      (node (ref "U15") (pin "3") (pinfunction "CSEL_3") (pintype "input"))
      (node (ref "U5") (pin "5") (pinfunction "D_5") (pintype "input"))
      (node (ref "U6") (pin "1") (pinfunction "1_1") (pintype "input"))
      (node (ref "U7") (pin "4") (pinfunction "VOUT_4") (pintype "input"))
    )
    (net (code "2") (name "433_IN") (class "Default")
      (node (ref "H9") (pin "1") (pinfunction "1_1") (pintype "unspecified"))
      (node (ref "R14") (pin "2") (pinfunction "2_2") (pintype "input"))
      (node (ref "U1") (pin "20") (pinfunction "PB2_20") (pintype "input"))
    )
    (net (code "3") (name "433_OUT") (class "Default")
      (node (ref "H10") (pin "1") (pinfunction "1_1") (pintype "unspecified"))
      (node (ref "R5") (pin "2") (pinfunction "2_2") (pintype "input"))
      (node (ref "U1") (pin "18") (pinfunction "PB0_18") (pintype "input"))
    )
    (net (code "4") (name "BOOT0") (class "Default")
      (node (ref "R11") (pin "2") (pinfunction "2_2") (pintype "input"))
      (node (ref "R9") (pin "2") (pinfunction "2_2") (pintype "input"))
      (node (ref "U1") (pin "44") (pinfunction "BOOT0_44") (pintype "input"))
    )
    (net (code "5") (name "BOOT1") (class "Default")
      (node (ref "R10") (pin "2") (pinfunction "2_2") (pintype "input"))
      (node (ref "U1") (pin "19") (pinfunction "PB1_19") (pintype "input"))
    )
    (net (code "6") (name "EN") (class "Default")
      (node (ref "L6") (pin "3") (pinfunction "EN_3") (pintype "input"))
      (node (ref "R2") (pin "1") (pinfunction "1_1") (pintype "input"))
      (node (ref "SW4") (pin "4") (pinfunction "4_4") (pintype "input"))
    )
    (net (code "7") (name "ESP32_RXD") (class "Default")
      (node (ref "H3") (pin "1") (pinfunction "1_1") (pintype "input"))
      (node (ref "H6") (pin "2") (pinfunction "2_2") (pintype "input"))
      (node (ref "L6") (pin "34") (pinfunction "U0RXD_34") (pintype "input"))
    )
    (net (code "8") (name "ESP32_TXD") (class "Default")
      (node (ref "H3") (pin "2") (pinfunction "2_2") (pintype "input"))
      (node (ref "H5") (pin "2") (pinfunction "2_2") (pintype "input"))
      (node (ref "L6") (pin "35") (pinfunction "U0TXD_35") (pintype "input"))
    )
    (net (code "9") (name "GND") (class "Default")
      (node (ref "C1") (pin "2") (pinfunction "2_2") (pintype "input"))
      (node (ref "C10") (pin "2") (pinfunction "2_2") (pintype "input"))
      (node (ref "C11") (pin "2") (pinfunction "2_2") (pintype "input"))
      (node (ref "C12") (pin "2") (pinfunction "2_2") (pintype "input"))
      (node (ref "C13") (pin "2") (pinfunction "2_2") (pintype "input"))
      (node (ref "C14") (pin "2") (pinfunction "2_2") (pintype "input"))
      (node (ref "C15") (pin "2") (pinfunction "2_2") (pintype "input"))
      (node (ref "C19") (pin "2") (pinfunction "2_2") (pintype "input"))
      (node (ref "C2") (pin "2") (pinfunction "2_2") (pintype "input"))
      (node (ref "C20") (pin "2") (pinfunction "2_2") (pintype "input"))
      (node (ref "C3") (pin "2") (pinfunction "2_2") (pintype "input"))
      (node (ref "C4") (pin "2") (pinfunction "2_2") (pintype "input"))
      (node (ref "C5") (pin "1") (pinfunction "1_1") (pintype "input"))
      (node (ref "C6") (pin "1") (pinfunction "1_1") (pintype "input"))
      (node (ref "C7") (pin "1") (pinfunction "1_1") (pintype "input"))
      (node (ref "C8") (pin "1") (pinfunction "1_1") (pintype "input"))
      (node (ref "C9") (pin "2") (pinfunction "2_2") (pintype "input"))
      (node (ref "DC1") (pin "2") (pinfunction "2_2") (pintype "input"))
      (node (ref "DC1") (pin "3") (pinfunction "3_3") (pintype "input"))
      (node (ref "H1") (pin "4") (pinfunction "4_4") (pintype "input"))
      (node (ref "H2") (pin "3") (pinfunction "3_3") (pintype "input"))
      (node (ref "H3") (pin "3") (pinfunction "3_3") (pintype "input"))
      (node (ref "H4") (pin "3") (pinfunction "3_3") (pintype "input"))
      (node (ref "H7") (pin "1") (pinfunction "1_1") (pintype "input"))
      (node (ref "H8") (pin "1") (pinfunction "1_1") (pintype "input"))
      (node (ref "H8") (pin "2") (pinfunction "2_2") (pintype "input"))
      (node (ref "L3") (pin "1") (pinfunction "1_1") (pintype "input"))
      (node (ref "L4") (pin "1") (pinfunction "1_1") (pintype "input"))
      (node (ref "L6") (pin "1") (pinfunction "GND_1") (pintype "input"))
      (node (ref "L6") (pin "15") (pinfunction "GND_15") (pintype "input"))
      (node (ref "L6") (pin "38") (pinfunction "GND_38") (pintype "input"))
      (node (ref "R10") (pin "1") (pinfunction "1_1") (pintype "input"))
      (node (ref "R13") (pin "2") (pinfunction "2_2") (pintype "input"))
      (node (ref "R18") (pin "2") (pinfunction "2_2") (pintype "input"))
      (node (ref "R29") (pin "2") (pinfunction "2_2") (pintype "input"))
      (node (ref "R4") (pin "1") (pinfunction "1_1") (pintype "input"))
      (node (ref "R7") (pin "1") (pinfunction "1_1") (pintype "input"))
      (node (ref "R9") (pin "1") (pinfunction "1_1") (pintype "input"))
      (node (ref "SW1") (pin "2") (pinfunction "2_2") (pintype "input"))
      (node (ref "SW4") (pin "2") (pinfunction "2_2") (pintype "input"))
      (node (ref "U1") (pin "23") (pinfunction "VSS_1_23") (pintype "input"))
      (node (ref "U1") (pin "35") (pinfunction "VSS_2_35") (pintype "input"))
      (node (ref "U1") (pin "47") (pinfunction "VSS_3_47") (pintype "input"))
      (node (ref "U1") (pin "8") (pinfunction "VSSA_8") (pintype "input"))
      (node (ref "U14") (pin "2") (pinfunction "GND_2") (pintype "input"))
      (node (ref "U15") (pin "1") (pinfunction "GND_1") (pintype "input"))
      (node (ref "U16") (pin "1") (pinfunction "1_1") (pintype "input"))
      (node (ref "U3") (pin "1") (pinfunction "1_1") (pintype "input"))
      (node (ref "U4") (pin "1") (pinfunction "1_1") (pintype "input"))
      (node (ref "U5") (pin "2") (pinfunction "D_2") (pintype "input"))
      (node (ref "U6") (pin "2") (pinfunction "2_2") (pintype "input"))
      (node (ref "U7") (pin "1") (pinfunction "ADJ/GND_1") (pintype "input"))
      (node (ref "X3") (pin "2") (pinfunction "GND_2") (pintype "input"))
      (node (ref "X3") (pin "4") (pinfunction "GND_4") (pintype "input"))
      (node (ref "X4") (pin "2") (pinfunction "2_2") (pintype "input"))
    )
    (net (code "10") (name "IO9") (class "Default")
      (node (ref "L6") (pin "25") (pinfunction "IO9_25") (pintype "input"))
      (node (ref "R3") (pin "1") (pinfunction "1_1") (pintype "input"))
      (node (ref "SW1") (pin "4") (pinfunction "4_4") (pintype "input"))
    )
    (net (code "11") (name "IR") (class "Default")
      (node (ref "U1") (pin "39") (pinfunction "PB3_39") (pintype "input"))
      (node (ref "U14") (pin "1") (pinfunction "VOUT_1") (pintype "input"))
    )
    (net (code "12") (name "LED_EN") (class "Default")
      (node (ref "LED5") (pin "1") (pinfunction "A_1") (pintype "input"))
      (node (ref "U1") (pin "11") (pinfunction "PA1_11") (pintype "input"))
    )
    (net (code "13") (name "MOTOR") (class "Default")
      (node (ref "H7") (pin "3") (pinfunction "3_3") (pintype "input"))
      (node (ref "R6") (pin "2") (pinfunction "2_2") (pintype "input"))
      (node (ref "U1") (pin "22") (pinfunction "PB11_22") (pintype "input"))
    )
    (net (code "14") (name "NRST") (class "Default")
      (node (ref "C19") (pin "1") (pinfunction "1_1") (pintype "input"))
      (node (ref "R18") (pin "1") (pinfunction "1_1") (pintype "input"))
      (node (ref "R8") (pin "1") (pinfunction "1_1") (pintype "input"))
      (node (ref "U1") (pin "7") (pinfunction "NRST_7") (pintype "input"))
    )
    (net (code "15") (name "Net-(ANT_发射-Pad1)") (class "Default")
      (node (ref "ANT_发射") (pin "1") (pinfunction "1_1") (pintype "unspecified"))
      (node (ref "L7") (pin "1") (pinfunction "1_1") (pintype "input"))
      (node (ref "U3") (pin "2") (pinfunction "2_2") (pintype "input"))
    )
    (net (code "16") (name "Net-(ANT_接收-Pad1)") (class "Default")
      (node (ref "ANT_接收") (pin "1") (pinfunction "1_1") (pintype "unspecified"))
      (node (ref "C11") (pin "1") (pinfunction "1_1") (pintype "input"))
      (node (ref "L3") (pin "2") (pinfunction "2_2") (pintype "input"))
      (node (ref "U8") (pin "2") (pinfunction "2_2") (pintype "input"))
    )
    (net (code "17") (name "Net-(C8-Pad2)") (class "Default")
      (node (ref "C8") (pin "2") (pinfunction "2_2") (pintype "input"))
      (node (ref "X1") (pin "2") (pinfunction "GND_2") (pintype "input"))
    )
    (net (code "18") (name "Net-(C9-Pad1)") (class "Default")
      (node (ref "C9") (pin "1") (pinfunction "1_1") (pintype "input"))
      (node (ref "X1") (pin "4") (pinfunction "GND_4") (pintype "input"))
    )
    (net (code "19") (name "Net-(C21-Pad2)") (class "Default")
      (node (ref "C21") (pin "2") (pinfunction "2_2") (pintype "input"))
      (node (ref "L1") (pin "2") (pinfunction "2_2") (pintype "input"))
    )
    (net (code "20") (name "Net-(DC1-Pad1)") (class "Default")
      (node (ref "DC1") (pin "1") (pinfunction "1_1") (pintype "input"))
      (node (ref "SW2") (pin "1") (pinfunction "1_1") (pintype "input"))
    )
    (net (code "21") (name "Net-(L1-Pad1)") (class "Default")
      (node (ref "L1") (pin "1") (pinfunction "1_1") (pintype "input"))
      (node (ref "L7") (pin "2") (pinfunction "2_2") (pintype "input"))
      (node (ref "U4") (pin "2") (pinfunction "2_2") (pintype "input"))
    )
    (net (code "22") (name "Net-(LED5-K)") (class "Default")
      (node (ref "LED5") (pin "2") (pinfunction "K_2") (pintype "input"))
      (node (ref "R29") (pin "1") (pinfunction "1_1") (pintype "input"))
    )
    (net (code "23") (name "Net-(R11-Pad1)") (class "Default")
      (node (ref "R11") (pin "1") (pinfunction "1_1") (pintype "input"))
      (node (ref "R21") (pin "1") (pinfunction "1_1") (pintype "input"))
    )
    (net (code "24") (name "Net-(U5-G1)") (class "Default")
      (node (ref "U5") (pin "6") (pinfunction "G1_6") (pintype "input"))
      (node (ref "X1") (pin "1") (pinfunction "1_1") (pintype "input"))
    )
    (net (code "25") (name "Net-(U5-G2)") (class "Default")
      (node (ref "R4") (pin "2") (pinfunction "2_2") (pintype "input"))
      (node (ref "R5") (pin "1") (pinfunction "1_1") (pintype "input"))
      (node (ref "U5") (pin "4") (pinfunction "G2_4") (pintype "input"))
    )
    (net (code "26") (name "Net-(U5-S1)") (class "Default")
      (node (ref "U5") (pin "1") (pinfunction "S1_1") (pintype "input"))
      (node (ref "X1") (pin "3") (pinfunction "3_3") (pintype "input"))
    )
    (net (code "27") (name "Net-(U5-S2)") (class "Default")
      (node (ref "C21") (pin "1") (pinfunction "1_1") (pintype "input"))
      (node (ref "L2") (pin "2") (pinfunction "2_2") (pintype "input"))
      (node (ref "U5") (pin "3") (pinfunction "S2_3") (pintype "input"))
    )
    (net (code "28") (name "Net-(U15-C1)") (class "Default")
      (node (ref "L4") (pin "2") (pinfunction "2_2") (pintype "input"))
      (node (ref "U15") (pin "2") (pinfunction "C1_2") (pintype "input"))
      (node (ref "U8") (pin "1") (pinfunction "1_1") (pintype "input"))
    )
    (net (code "29") (name "Net-(U15-OUT1)") (class "Default")
      (node (ref "R7") (pin "2") (pinfunction "2_2") (pintype "input"))
      (node (ref "U15") (pin "6") (pinfunction "OUT1_6") (pintype "input"))
    )
    (net (code "30") (name "Net-(U15-PAD0)") (class "Default")
      (node (ref "U15") (pin "4") (pinfunction "PAD0_4") (pintype "input"))
      (node (ref "U16") (pin "2") (pinfunction "2_2") (pintype "input"))
    )
    (net (code "31") (name "Net-(U15-PAD1)") (class "Default")
      (node (ref "R14") (pin "1") (pinfunction "1_1") (pintype "input"))
      (node (ref "U15") (pin "5") (pinfunction "PAD1_5") (pintype "input"))
    )
    (net (code "32") (name "Net-(U15-VDD)") (class "Default")
      (node (ref "U15") (pin "8") (pinfunction "VDD_8") (pintype "input"))
      (node (ref "X4") (pin "1") (pinfunction "1_1") (pintype "input"))
    )
    (net (code "33") (name "OSC_IN") (class "Default")
      (node (ref "C6") (pin "2") (pinfunction "2_2") (pintype "input"))
      (node (ref "U1") (pin "5") (pinfunction "PD0-OSC_IN_5") (pintype "input"))
      (node (ref "X3") (pin "1") (pinfunction "1_1") (pintype "input"))
    )
    (net (code "34") (name "OSC_OUT") (class "Default")
      (node (ref "C5") (pin "2") (pinfunction "2_2") (pintype "input"))
      (node (ref "U1") (pin "6") (pinfunction "PD1-OSC_OUT_6") (pintype "input"))
      (node (ref "X3") (pin "3") (pinfunction "3_3") (pintype "input"))
    )
    (net (code "35") (name "RDX") (class "Default")
      (node (ref "H4") (pin "1") (pinfunction "1_1") (pintype "input"))
      (node (ref "U1") (pin "13") (pinfunction "PA3_13") (pintype "input"))
    )
    (net (code "36") (name "STM32_RDX") (class "Default")
      (node (ref "H2") (pin "1") (pinfunction "1_1") (pintype "input"))
      (node (ref "H5") (pin "1") (pinfunction "1_1") (pintype "input"))
      (node (ref "U1") (pin "43") (pinfunction "PB7_43") (pintype "input"))
    )
    (net (code "37") (name "STM32_TDX") (class "Default")
      (node (ref "H2") (pin "2") (pinfunction "2_2") (pintype "input"))
      (node (ref "H6") (pin "1") (pinfunction "1_1") (pintype "input"))
      (node (ref "U1") (pin "42") (pinfunction "PB6_42") (pintype "input"))
    )
    (net (code "38") (name "SWCLK") (class "Default")
      (node (ref "H1") (pin "3") (pinfunction "3_3") (pintype "input"))
      (node (ref "R13") (pin "1") (pinfunction "1_1") (pintype "input"))
      (node (ref "U1") (pin "37") (pinfunction "PA14_37") (pintype "input"))
    )
    (net (code "39") (name "SWDIO") (class "Default")
      (node (ref "H1") (pin "2") (pinfunction "2_2") (pintype "input"))
      (node (ref "R12") (pin "1") (pinfunction "1_1") (pintype "input"))
      (node (ref "U1") (pin "34") (pinfunction "PA13_34") (pintype "input"))
    )
    (net (code "40") (name "TDX") (class "Default")
      (node (ref "H4") (pin "2") (pinfunction "2_2") (pintype "input"))
      (node (ref "U1") (pin "12") (pinfunction "PA2_12") (pintype "input"))
    )
    (net (code "41") (name "VCC") (class "Default")
      (node (ref "C13") (pin "1") (pinfunction "1_1") (pintype "input"))
      (node (ref "C14") (pin "1") (pinfunction "1_1") (pintype "input"))
      (node (ref "H7") (pin "2") (pinfunction "2_2") (pintype "input"))
      (node (ref "R6") (pin "1") (pinfunction "1_1") (pintype "input"))
      (node (ref "SW2") (pin "2") (pinfunction "2_2") (pintype "input"))
      (node (ref "U14") (pin "3") (pinfunction "VCC_3") (pintype "input"))
      (node (ref "U7") (pin "3") (pinfunction "VIN_3") (pintype "input"))
    )
    (net (code "42") (name "unconnected-(L6-IO0-Pad5)") (class "Default")
      (node (ref "L6") (pin "5") (pinfunction "IO0_5") (pintype "input"))
    )
    (net (code "43") (name "unconnected-(L6-IO1-Pad6)") (class "Default")
      (node (ref "L6") (pin "6") (pinfunction "IO1_6") (pintype "input"))
    )
    (net (code "44") (name "unconnected-(L6-IO2-Pad7)") (class "Default")
      (node (ref "L6") (pin "7") (pinfunction "IO2_7") (pintype "input"))
    )
    (net (code "45") (name "unconnected-(L6-IO3-Pad8)") (class "Default")
      (node (ref "L6") (pin "8") (pinfunction "IO3_8") (pintype "input"))
    )
    (net (code "46") (name "unconnected-(L6-IO4-Pad9)") (class "Default")
      (node (ref "L6") (pin "9") (pinfunction "IO4_9") (pintype "input"))
    )
    (net (code "47") (name "unconnected-(L6-IO5-Pad10)") (class "Default")
      (node (ref "L6") (pin "10") (pinfunction "IO5_10") (pintype "input"))
    )
    (net (code "48") (name "unconnected-(L6-IO6-Pad11)") (class "Default")
      (node (ref "L6") (pin "11") (pinfunction "IO6_11") (pintype "input"))
    )
    (net (code "49") (name "unconnected-(L6-IO7-Pad12)") (class "Default")
      (node (ref "L6") (pin "12") (pinfunction "IO7_12") (pintype "input"))
    )
    (net (code "50") (name "unconnected-(L6-IO8-Pad13)") (class "Default")
      (node (ref "L6") (pin "13") (pinfunction "IO8_13") (pintype "input"))
    )
    (net (code "51") (name "unconnected-(L6-IO10-Pad14)") (class "Default")
      (node (ref "L6") (pin "14") (pinfunction "IO10_14") (pintype "input"))
    )
    (net (code "52") (name "unconnected-(L6-IO18-Pad30)") (class "Default")
      (node (ref "L6") (pin "30") (pinfunction "IO18_30") (pintype "input"))
    )
    (net (code "53") (name "unconnected-(L6-IO19-Pad31)") (class "Default")
      (node (ref "L6") (pin "31") (pinfunction "IO19_31") (pintype "input"))
    )
    (net (code "54") (name "unconnected-(L6-NC-Pad4)") (class "Default")
      (node (ref "L6") (pin "4") (pinfunction "NC_4") (pintype "input"))
    )
    (net (code "55") (name "unconnected-(L6-NC-Pad16)") (class "Default")
      (node (ref "L6") (pin "16") (pinfunction "NC_16") (pintype "input"))
    )
    (net (code "56") (name "unconnected-(L6-NC-Pad23)") (class "Default")
      (node (ref "L6") (pin "23") (pinfunction "NC_23") (pintype "input"))
    )
    (net (code "57") (name "unconnected-(L6-NC-Pad24)") (class "Default")
      (node (ref "L6") (pin "24") (pinfunction "NC_24") (pintype "input"))
    )
    (net (code "58") (name "unconnected-(L6-NC-Pad26)") (class "Default")
      (node (ref "L6") (pin "26") (pinfunction "NC_26") (pintype "input"))
    )
    (net (code "59") (name "unconnected-(L6-NC-Pad27)") (class "Default")
      (node (ref "L6") (pin "27") (pinfunction "NC_27") (pintype "input"))
    )
    (net (code "60") (name "unconnected-(L6-NC-Pad28)") (class "Default")
      (node (ref "L6") (pin "28") (pinfunction "NC_28") (pintype "input"))
    )
    (net (code "61") (name "unconnected-(L6-NC-Pad29)") (class "Default")
      (node (ref "L6") (pin "29") (pinfunction "NC_29") (pintype "input"))
    )
    (net (code "62") (name "unconnected-(L6-NC-Pad32)") (class "Default")
      (node (ref "L6") (pin "32") (pinfunction "NC_32") (pintype "input"))
    )
    (net (code "63") (name "unconnected-(L6-NC-Pad33)") (class "Default")
      (node (ref "L6") (pin "33") (pinfunction "NC_33") (pintype "input"))
    )
    (net (code "64") (name "unconnected-(L6-NC-Pad36)") (class "Default")
      (node (ref "L6") (pin "36") (pinfunction "NC_36") (pintype "input"))
    )
    (net (code "65") (name "unconnected-(L6-NC-Pad37)") (class "Default")
      (node (ref "L6") (pin "37") (pinfunction "NC_37") (pintype "input"))
    )
    (net (code "66") (name "unconnected-(L6-SPICLK-Pad20)") (class "Default")
      (node (ref "L6") (pin "20") (pinfunction "SPICLK_20") (pintype "input"))
    )
    (net (code "67") (name "unconnected-(L6-SPICS0-Pad19)") (class "Default")
      (node (ref "L6") (pin "19") (pinfunction "SPICS0_19") (pintype "input"))
    )
    (net (code "68") (name "unconnected-(L6-SPID-Pad22)") (class "Default")
      (node (ref "L6") (pin "22") (pinfunction "SPID_22") (pintype "input"))
    )
    (net (code "69") (name "unconnected-(L6-SPIHD-Pad17)") (class "Default")
      (node (ref "L6") (pin "17") (pinfunction "SPIHD_17") (pintype "input"))
    )
    (net (code "70") (name "unconnected-(L6-SPIQ-Pad21)") (class "Default")
      (node (ref "L6") (pin "21") (pinfunction "SPIQ_21") (pintype "input"))
    )
    (net (code "71") (name "unconnected-(L6-SPIWP-Pad18)") (class "Default")
      (node (ref "L6") (pin "18") (pinfunction "SPIWP_18") (pintype "input"))
    )
    (net (code "72") (name "unconnected-(SW1-Pad1)") (class "Default")
      (node (ref "SW1") (pin "1") (pinfunction "1_1") (pintype "input"))
    )
    (net (code "73") (name "unconnected-(SW1-Pad3)") (class "Default")
      (node (ref "SW1") (pin "3") (pinfunction "3_3") (pintype "input"))
    )
    (net (code "74") (name "unconnected-(SW2-Pad3)") (class "Default")
      (node (ref "SW2") (pin "3") (pinfunction "3_3") (pintype "input"))
    )
    (net (code "75") (name "unconnected-(SW4-Pad1)") (class "Default")
      (node (ref "SW4") (pin "1") (pinfunction "1_1") (pintype "input"))
    )
    (net (code "76") (name "unconnected-(SW4-Pad3)") (class "Default")
      (node (ref "SW4") (pin "3") (pinfunction "3_3") (pintype "input"))
    )
    (net (code "77") (name "unconnected-(U1-PA0-WKUP-Pad10)") (class "Default")
      (node (ref "U1") (pin "10") (pinfunction "PA0-WKUP_10") (pintype "input"))
    )
    (net (code "78") (name "unconnected-(U1-PA4-Pad14)") (class "Default")
      (node (ref "U1") (pin "14") (pinfunction "PA4_14") (pintype "input"))
    )
    (net (code "79") (name "unconnected-(U1-PA5-Pad15)") (class "Default")
      (node (ref "U1") (pin "15") (pinfunction "PA5_15") (pintype "input"))
    )
    (net (code "80") (name "unconnected-(U1-PA6-Pad16)") (class "Default")
      (node (ref "U1") (pin "16") (pinfunction "PA6_16") (pintype "input"))
    )
    (net (code "81") (name "unconnected-(U1-PA7-Pad17)") (class "Default")
      (node (ref "U1") (pin "17") (pinfunction "PA7_17") (pintype "input"))
    )
    (net (code "82") (name "unconnected-(U1-PA8-Pad29)") (class "Default")
      (node (ref "U1") (pin "29") (pinfunction "PA8_29") (pintype "input"))
    )
    (net (code "83") (name "unconnected-(U1-PA9-Pad30)") (class "Default")
      (node (ref "U1") (pin "30") (pinfunction "PA9_30") (pintype "input"))
    )
    (net (code "84") (name "unconnected-(U1-PA10-Pad31)") (class "Default")
      (node (ref "U1") (pin "31") (pinfunction "PA10_31") (pintype "input"))
    )
    (net (code "85") (name "unconnected-(U1-PA11-Pad32)") (class "Default")
      (node (ref "U1") (pin "32") (pinfunction "PA11_32") (pintype "input"))
    )
    (net (code "86") (name "unconnected-(U1-PA12-Pad33)") (class "Default")
      (node (ref "U1") (pin "33") (pinfunction "PA12_33") (pintype "input"))
    )
    (net (code "87") (name "unconnected-(U1-PA15-Pad38)") (class "Default")
      (node (ref "U1") (pin "38") (pinfunction "PA15_38") (pintype "input"))
    )
    (net (code "88") (name "unconnected-(U1-PB4-Pad40)") (class "Default")
      (node (ref "U1") (pin "40") (pinfunction "PB4_40") (pintype "input"))
    )
    (net (code "89") (name "unconnected-(U1-PB5-Pad41)") (class "Default")
      (node (ref "U1") (pin "41") (pinfunction "PB5_41") (pintype "input"))
    )
    (net (code "90") (name "unconnected-(U1-PB8-Pad45)") (class "Default")
      (node (ref "U1") (pin "45") (pinfunction "PB8_45") (pintype "input"))
    )
    (net (code "91") (name "unconnected-(U1-PB9-Pad46)") (class "Default")
      (node (ref "U1") (pin "46") (pinfunction "PB9_46") (pintype "input"))
    )
    (net (code "92") (name "unconnected-(U1-PB10-Pad21)") (class "Default")
      (node (ref "U1") (pin "21") (pinfunction "PB10_21") (pintype "input"))
    )
    (net (code "93") (name "unconnected-(U1-PB12-Pad25)") (class "Default")
      (node (ref "U1") (pin "25") (pinfunction "PB12_25") (pintype "input"))
    )
    (net (code "94") (name "unconnected-(U1-PB13-Pad26)") (class "Default")
      (node (ref "U1") (pin "26") (pinfunction "PB13_26") (pintype "input"))
    )
    (net (code "95") (name "unconnected-(U1-PB14-Pad27)") (class "Default")
      (node (ref "U1") (pin "27") (pinfunction "PB14_27") (pintype "input"))
    )
    (net (code "96") (name "unconnected-(U1-PB15-Pad28)") (class "Default")
      (node (ref "U1") (pin "28") (pinfunction "PB15_28") (pintype "input"))
    )
    (net (code "97") (name "unconnected-(U1-PC13-TAMPER-RTC-Pad2)") (class "Default")
      (node (ref "U1") (pin "2") (pinfunction "PC13-TAMPER-RTC_2") (pintype "input"))
    )
    (net (code "98") (name "unconnected-(U1-PC14-OSC32_IN-Pad3)") (class "Default")
      (node (ref "U1") (pin "3") (pinfunction "PC14-OSC32_IN_3") (pintype "input"))
    )
    (net (code "99") (name "unconnected-(U1-PC15-OSC32_OUT-Pad4)") (class "Default")
      (node (ref "U1") (pin "4") (pinfunction "PC15-OSC32_OUT_4") (pintype "input"))
    )
    (net (code "100") (name "unconnected-(U7-VOUT-Pad2)") (class "Default")
      (node (ref "U7") (pin "2") (pinfunction "VOUT_2") (pintype "input"))
    )
    (net (code "101") (name "unconnected-(U15-OUT0-Pad7)") (class "Default")
      (node (ref "U15") (pin "7") (pinfunction "OUT0_7") (pintype "input"))
    )
  )
)
